# enigma.net
KiCad netlist of a schematic drawn in EAGLE
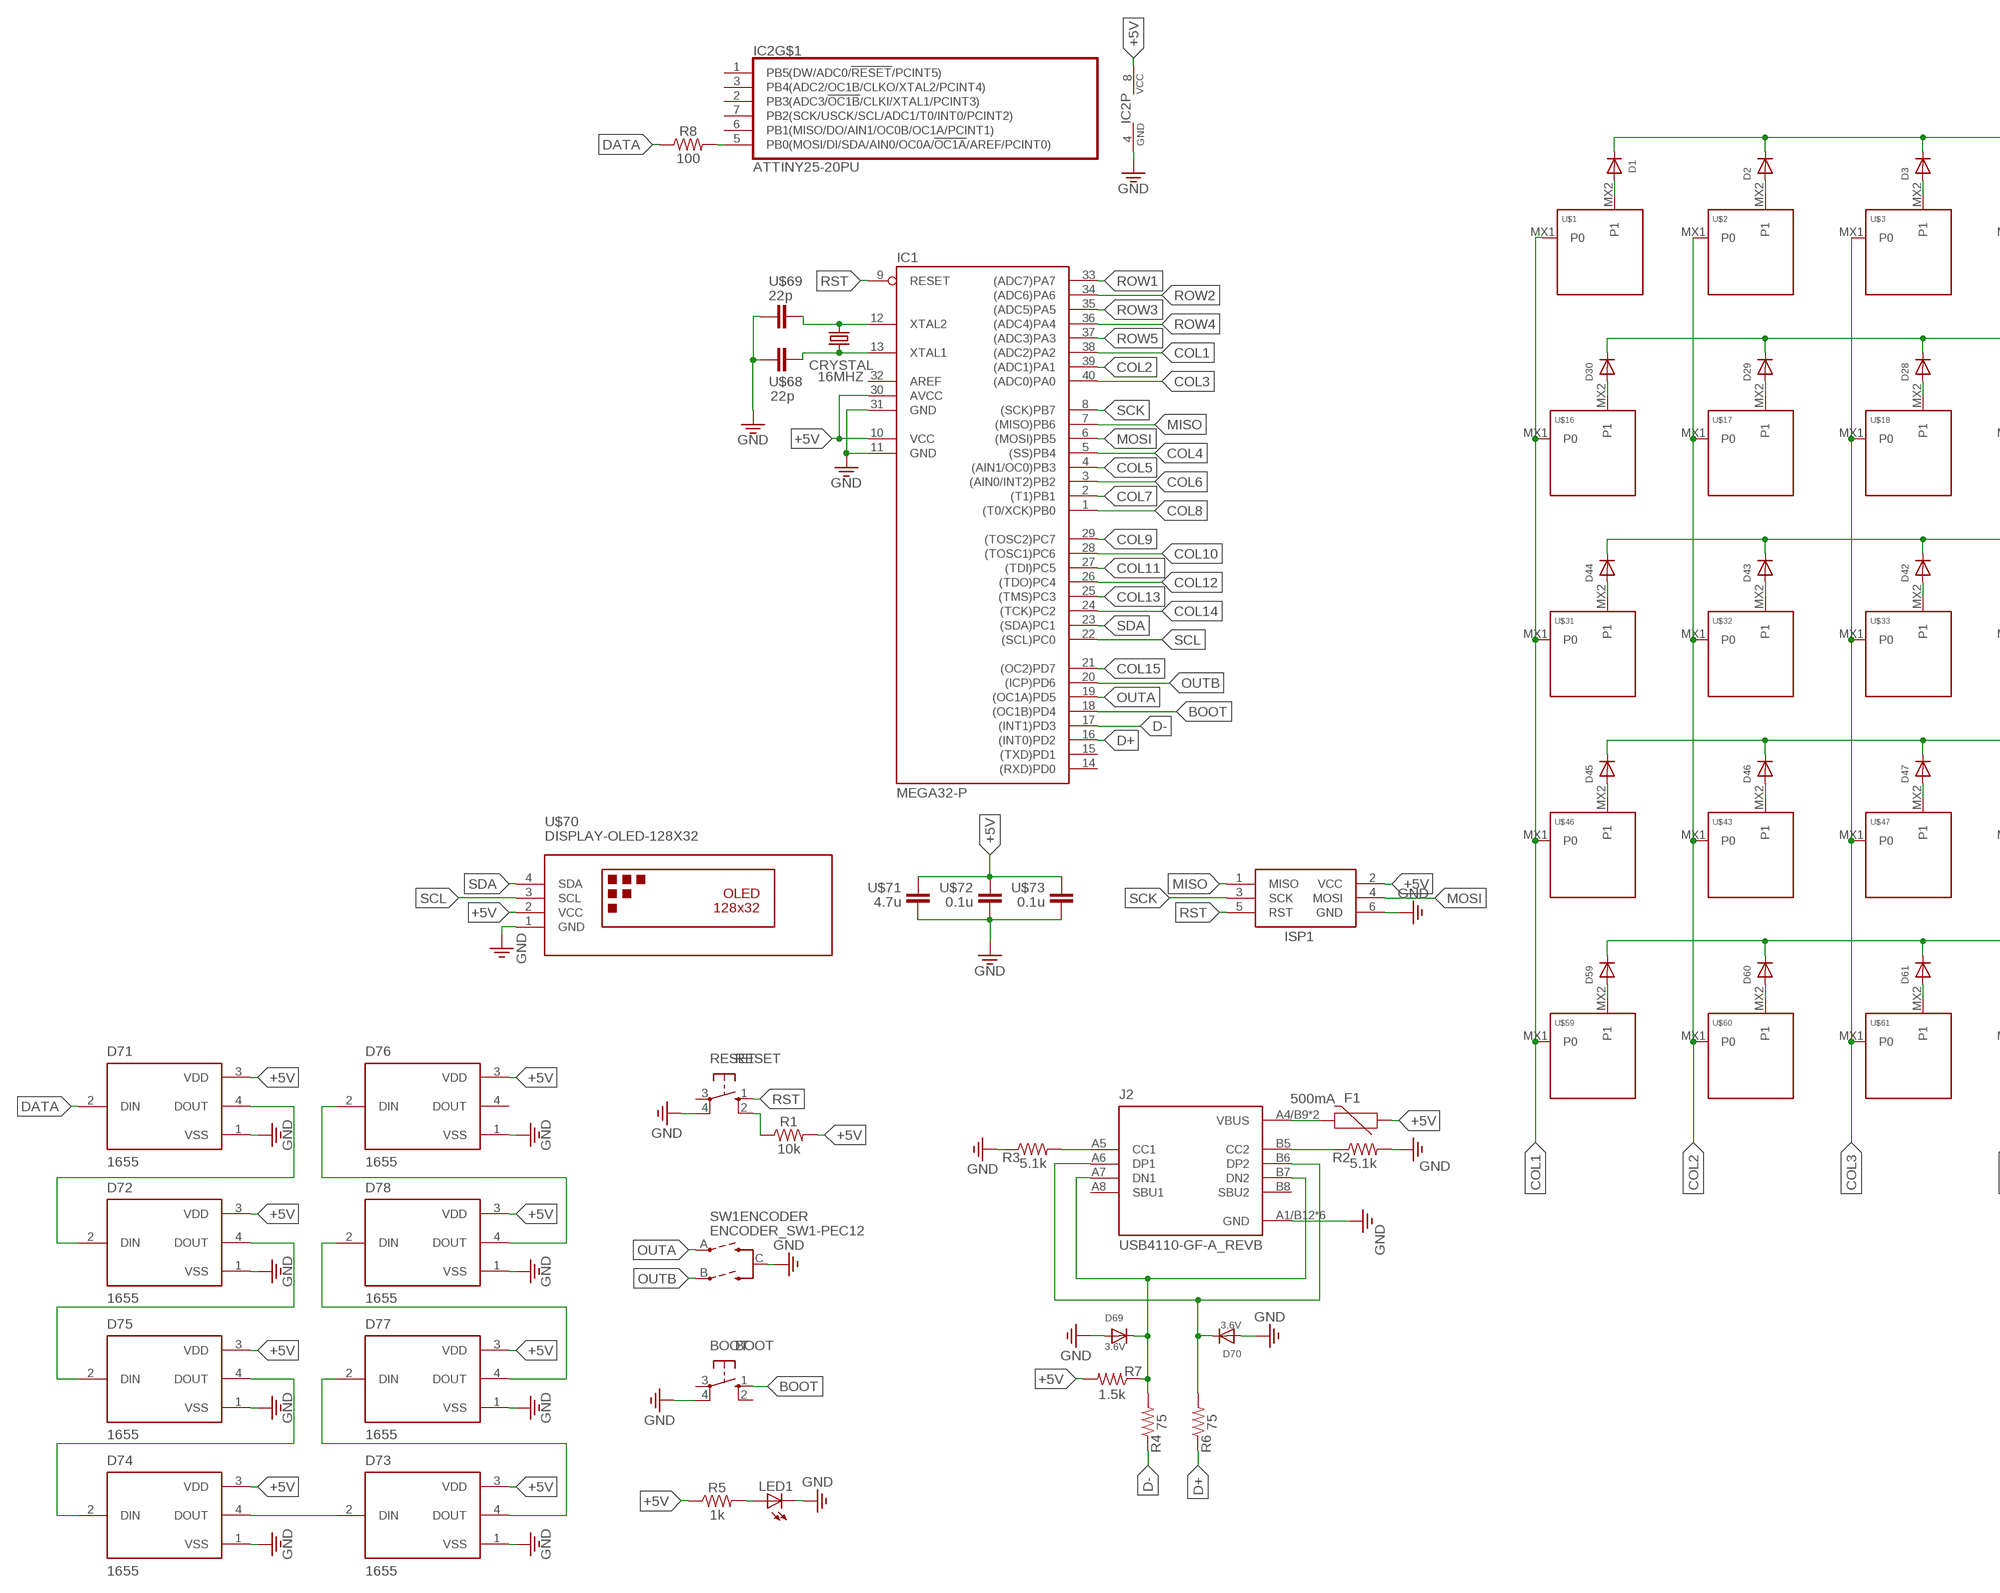
[diagram p0: schematic, sheet 1, part 1 of 2]
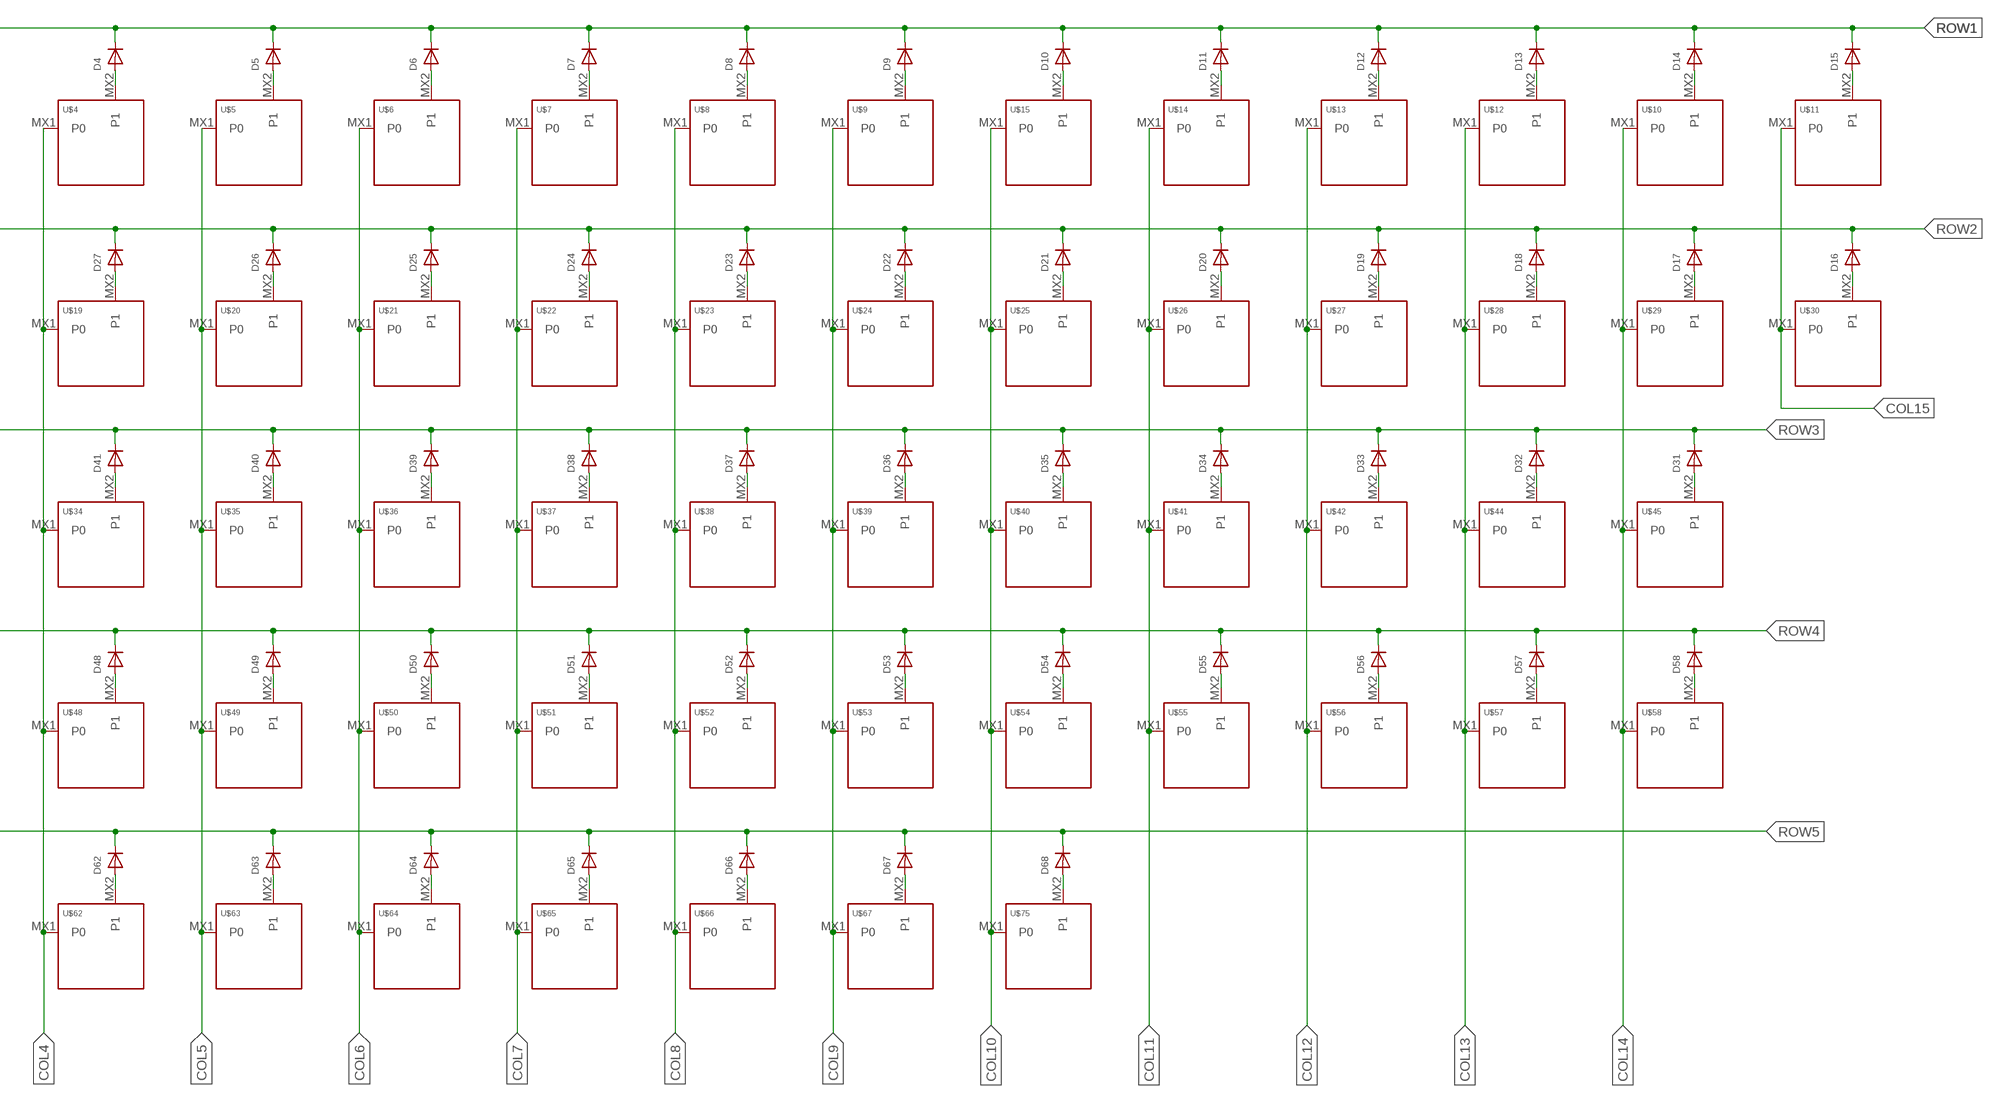
[diagram p1: schematic, sheet 1, part 2 of 2]

(export (version "E")
  (design (tool "Eeschema 10.0.6"))
  (components
    (comp (ref "BOOT")
      (value "BOOT")
      (footprint "eagle-import:B3F-10XX")
      (fields (field (name "MPN") "B3F-1000"))
      (libsource (lib "eagle-import") (part "10-XX"))
    )
    (comp (ref "CRYSTAL")
      (value "16MHZ")
      (footprint "eagle-import:HC49U-V")
      (libsource (lib "eagle-import") (part "CRYSTALHC49U-V"))
    )
    (comp (ref "D1")
      (value "DIODEDO-1N4148")
      (footprint "eagle-import:DO-1N4148")
      (libsource (lib "eagle-import") (part "DIODEDO-1N4148"))
    )
    (comp (ref "D2")
      (value "DIODEDO-1N4148")
      (footprint "eagle-import:DO-1N4148")
      (libsource (lib "eagle-import") (part "DIODEDO-1N4148"))
    )
    (comp (ref "D3")
      (value "DIODEDO-1N4148")
      (footprint "eagle-import:DO-1N4148")
      (libsource (lib "eagle-import") (part "DIODEDO-1N4148"))
    )
    (comp (ref "D4")
      (value "DIODEDO-1N4148")
      (footprint "eagle-import:DO-1N4148")
      (libsource (lib "eagle-import") (part "DIODEDO-1N4148"))
    )
    (comp (ref "D5")
      (value "DIODEDO-1N4148")
      (footprint "eagle-import:DO-1N4148")
      (libsource (lib "eagle-import") (part "DIODEDO-1N4148"))
    )
    (comp (ref "D6")
      (value "DIODEDO-1N4148")
      (footprint "eagle-import:DO-1N4148")
      (libsource (lib "eagle-import") (part "DIODEDO-1N4148"))
    )
    (comp (ref "D7")
      (value "DIODEDO-1N4148")
      (footprint "eagle-import:DO-1N4148")
      (libsource (lib "eagle-import") (part "DIODEDO-1N4148"))
    )
    (comp (ref "D8")
      (value "DIODEDO-1N4148")
      (footprint "eagle-import:DO-1N4148")
      (libsource (lib "eagle-import") (part "DIODEDO-1N4148"))
    )
    (comp (ref "D9")
      (value "DIODEDO-1N4148")
      (footprint "eagle-import:DO-1N4148")
      (libsource (lib "eagle-import") (part "DIODEDO-1N4148"))
    )
    (comp (ref "D10")
      (value "DIODEDO-1N4148")
      (footprint "eagle-import:DO-1N4148")
      (libsource (lib "eagle-import") (part "DIODEDO-1N4148"))
    )
    (comp (ref "D11")
      (value "DIODEDO-1N4148")
      (footprint "eagle-import:DO-1N4148")
      (libsource (lib "eagle-import") (part "DIODEDO-1N4148"))
    )
    (comp (ref "D12")
      (value "DIODEDO-1N4148")
      (footprint "eagle-import:DO-1N4148")
      (libsource (lib "eagle-import") (part "DIODEDO-1N4148"))
    )
    (comp (ref "D13")
      (value "DIODEDO-1N4148")
      (footprint "eagle-import:DO-1N4148")
      (libsource (lib "eagle-import") (part "DIODEDO-1N4148"))
    )
    (comp (ref "D14")
      (value "DIODEDO-1N4148")
      (footprint "eagle-import:DO-1N4148")
      (libsource (lib "eagle-import") (part "DIODEDO-1N4148"))
    )
    (comp (ref "D15")
      (value "DIODEDO-1N4148")
      (footprint "eagle-import:DO-1N4148")
      (libsource (lib "eagle-import") (part "DIODEDO-1N4148"))
    )
    (comp (ref "D16")
      (value "DIODEDO-1N4148")
      (footprint "eagle-import:DO-1N4148")
      (libsource (lib "eagle-import") (part "DIODEDO-1N4148"))
    )
    (comp (ref "D17")
      (value "DIODEDO-1N4148")
      (footprint "eagle-import:DO-1N4148")
      (libsource (lib "eagle-import") (part "DIODEDO-1N4148"))
    )
    (comp (ref "D18")
      (value "DIODEDO-1N4148")
      (footprint "eagle-import:DO-1N4148")
      (libsource (lib "eagle-import") (part "DIODEDO-1N4148"))
    )
    (comp (ref "D19")
      (value "DIODEDO-1N4148")
      (footprint "eagle-import:DO-1N4148")
      (libsource (lib "eagle-import") (part "DIODEDO-1N4148"))
    )
    (comp (ref "D20")
      (value "DIODEDO-1N4148")
      (footprint "eagle-import:DO-1N4148")
      (libsource (lib "eagle-import") (part "DIODEDO-1N4148"))
    )
    (comp (ref "D21")
      (value "DIODEDO-1N4148")
      (footprint "eagle-import:DO-1N4148")
      (libsource (lib "eagle-import") (part "DIODEDO-1N4148"))
    )
    (comp (ref "D22")
      (value "DIODEDO-1N4148")
      (footprint "eagle-import:DO-1N4148")
      (libsource (lib "eagle-import") (part "DIODEDO-1N4148"))
    )
    (comp (ref "D23")
      (value "DIODEDO-1N4148")
      (footprint "eagle-import:DO-1N4148")
      (libsource (lib "eagle-import") (part "DIODEDO-1N4148"))
    )
    (comp (ref "D24")
      (value "DIODEDO-1N4148")
      (footprint "eagle-import:DO-1N4148")
      (libsource (lib "eagle-import") (part "DIODEDO-1N4148"))
    )
    (comp (ref "D25")
      (value "DIODEDO-1N4148")
      (footprint "eagle-import:DO-1N4148")
      (libsource (lib "eagle-import") (part "DIODEDO-1N4148"))
    )
    (comp (ref "D26")
      (value "DIODEDO-1N4148")
      (footprint "eagle-import:DO-1N4148")
      (libsource (lib "eagle-import") (part "DIODEDO-1N4148"))
    )
    (comp (ref "D27")
      (value "DIODEDO-1N4148")
      (footprint "eagle-import:DO-1N4148")
      (libsource (lib "eagle-import") (part "DIODEDO-1N4148"))
    )
    (comp (ref "D28")
      (value "DIODEDO-1N4148")
      (footprint "eagle-import:DO-1N4148")
      (libsource (lib "eagle-import") (part "DIODEDO-1N4148"))
    )
    (comp (ref "D29")
      (value "DIODEDO-1N4148")
      (footprint "eagle-import:DO-1N4148")
      (libsource (lib "eagle-import") (part "DIODEDO-1N4148"))
    )
    (comp (ref "D30")
      (value "DIODEDO-1N4148")
      (footprint "eagle-import:DO-1N4148")
      (libsource (lib "eagle-import") (part "DIODEDO-1N4148"))
    )
    (comp (ref "D31")
      (value "DIODEDO-1N4148")
      (footprint "eagle-import:DO-1N4148")
      (libsource (lib "eagle-import") (part "DIODEDO-1N4148"))
    )
    (comp (ref "D32")
      (value "DIODEDO-1N4148")
      (footprint "eagle-import:DO-1N4148")
      (libsource (lib "eagle-import") (part "DIODEDO-1N4148"))
    )
    (comp (ref "D33")
      (value "DIODEDO-1N4148")
      (footprint "eagle-import:DO-1N4148")
      (libsource (lib "eagle-import") (part "DIODEDO-1N4148"))
    )
    (comp (ref "D34")
      (value "DIODEDO-1N4148")
      (footprint "eagle-import:DO-1N4148")
      (libsource (lib "eagle-import") (part "DIODEDO-1N4148"))
    )
    (comp (ref "D35")
      (value "DIODEDO-1N4148")
      (footprint "eagle-import:DO-1N4148")
      (libsource (lib "eagle-import") (part "DIODEDO-1N4148"))
    )
    (comp (ref "D36")
      (value "DIODEDO-1N4148")
      (footprint "eagle-import:DO-1N4148")
      (libsource (lib "eagle-import") (part "DIODEDO-1N4148"))
    )
    (comp (ref "D37")
      (value "DIODEDO-1N4148")
      (footprint "eagle-import:DO-1N4148")
      (libsource (lib "eagle-import") (part "DIODEDO-1N4148"))
    )
    (comp (ref "D38")
      (value "DIODEDO-1N4148")
      (footprint "eagle-import:DO-1N4148")
      (libsource (lib "eagle-import") (part "DIODEDO-1N4148"))
    )
    (comp (ref "D39")
      (value "DIODEDO-1N4148")
      (footprint "eagle-import:DO-1N4148")
      (libsource (lib "eagle-import") (part "DIODEDO-1N4148"))
    )
    (comp (ref "D40")
      (value "DIODEDO-1N4148")
      (footprint "eagle-import:DO-1N4148")
      (libsource (lib "eagle-import") (part "DIODEDO-1N4148"))
    )
    (comp (ref "D41")
      (value "DIODEDO-1N4148")
      (footprint "eagle-import:DO-1N4148")
      (libsource (lib "eagle-import") (part "DIODEDO-1N4148"))
    )
    (comp (ref "D42")
      (value "DIODEDO-1N4148")
      (footprint "eagle-import:DO-1N4148")
      (libsource (lib "eagle-import") (part "DIODEDO-1N4148"))
    )
    (comp (ref "D43")
      (value "DIODEDO-1N4148")
      (footprint "eagle-import:DO-1N4148")
      (libsource (lib "eagle-import") (part "DIODEDO-1N4148"))
    )
    (comp (ref "D44")
      (value "DIODEDO-1N4148")
      (footprint "eagle-import:DO-1N4148")
      (libsource (lib "eagle-import") (part "DIODEDO-1N4148"))
    )
    (comp (ref "D45")
      (value "DIODEDO-1N4148")
      (footprint "eagle-import:DO-1N4148")
      (libsource (lib "eagle-import") (part "DIODEDO-1N4148"))
    )
    (comp (ref "D46")
      (value "DIODEDO-1N4148")
      (footprint "eagle-import:DO-1N4148")
      (libsource (lib "eagle-import") (part "DIODEDO-1N4148"))
    )
    (comp (ref "D47")
      (value "DIODEDO-1N4148")
      (footprint "eagle-import:DO-1N4148")
      (libsource (lib "eagle-import") (part "DIODEDO-1N4148"))
    )
    (comp (ref "D48")
      (value "DIODEDO-1N4148")
      (footprint "eagle-import:DO-1N4148")
      (libsource (lib "eagle-import") (part "DIODEDO-1N4148"))
    )
    (comp (ref "D49")
      (value "DIODEDO-1N4148")
      (footprint "eagle-import:DO-1N4148")
      (libsource (lib "eagle-import") (part "DIODEDO-1N4148"))
    )
    (comp (ref "D50")
      (value "DIODEDO-1N4148")
      (footprint "eagle-import:DO-1N4148")
      (libsource (lib "eagle-import") (part "DIODEDO-1N4148"))
    )
    (comp (ref "D51")
      (value "DIODEDO-1N4148")
      (footprint "eagle-import:DO-1N4148")
      (libsource (lib "eagle-import") (part "DIODEDO-1N4148"))
    )
    (comp (ref "D52")
      (value "DIODEDO-1N4148")
      (footprint "eagle-import:DO-1N4148")
      (libsource (lib "eagle-import") (part "DIODEDO-1N4148"))
    )
    (comp (ref "D53")
      (value "DIODEDO-1N4148")
      (footprint "eagle-import:DO-1N4148")
      (libsource (lib "eagle-import") (part "DIODEDO-1N4148"))
    )
    (comp (ref "D54")
      (value "DIODEDO-1N4148")
      (footprint "eagle-import:DO-1N4148")
      (libsource (lib "eagle-import") (part "DIODEDO-1N4148"))
    )
    (comp (ref "D55")
      (value "DIODEDO-1N4148")
      (footprint "eagle-import:DO-1N4148")
      (libsource (lib "eagle-import") (part "DIODEDO-1N4148"))
    )
    (comp (ref "D56")
      (value "DIODEDO-1N4148")
      (footprint "eagle-import:DO-1N4148")
      (libsource (lib "eagle-import") (part "DIODEDO-1N4148"))
    )
    (comp (ref "D57")
      (value "DIODEDO-1N4148")
      (footprint "eagle-import:DO-1N4148")
      (libsource (lib "eagle-import") (part "DIODEDO-1N4148"))
    )
    (comp (ref "D58")
      (value "DIODEDO-1N4148")
      (footprint "eagle-import:DO-1N4148")
      (libsource (lib "eagle-import") (part "DIODEDO-1N4148"))
    )
    (comp (ref "D59")
      (value "DIODEDO-1N4148")
      (footprint "eagle-import:DO-1N4148")
      (libsource (lib "eagle-import") (part "DIODEDO-1N4148"))
    )
    (comp (ref "D60")
      (value "DIODEDO-1N4148")
      (footprint "eagle-import:DO-1N4148")
      (libsource (lib "eagle-import") (part "DIODEDO-1N4148"))
    )
    (comp (ref "D61")
      (value "DIODEDO-1N4148")
      (footprint "eagle-import:DO-1N4148")
      (libsource (lib "eagle-import") (part "DIODEDO-1N4148"))
    )
    (comp (ref "D62")
      (value "DIODEDO-1N4148")
      (footprint "eagle-import:DO-1N4148")
      (libsource (lib "eagle-import") (part "DIODEDO-1N4148"))
    )
    (comp (ref "D63")
      (value "DIODEDO-1N4148")
      (footprint "eagle-import:DO-1N4148")
      (libsource (lib "eagle-import") (part "DIODEDO-1N4148"))
    )
    (comp (ref "D64")
      (value "DIODEDO-1N4148")
      (footprint "eagle-import:DO-1N4148")
      (libsource (lib "eagle-import") (part "DIODEDO-1N4148"))
    )
    (comp (ref "D65")
      (value "DIODEDO-1N4148")
      (footprint "eagle-import:DO-1N4148")
      (libsource (lib "eagle-import") (part "DIODEDO-1N4148"))
    )
    (comp (ref "D66")
      (value "DIODEDO-1N4148")
      (footprint "eagle-import:DO-1N4148")
      (libsource (lib "eagle-import") (part "DIODEDO-1N4148"))
    )
    (comp (ref "D67")
      (value "DIODEDO-1N4148")
      (footprint "eagle-import:DO-1N4148")
      (libsource (lib "eagle-import") (part "DIODEDO-1N4148"))
    )
    (comp (ref "D68")
      (value "DIODEDO-1N4148")
      (footprint "eagle-import:DO-1N4148")
      (libsource (lib "eagle-import") (part "DIODEDO-1N4148"))
    )
    (comp (ref "D69")
      (value "3.6V")
      (footprint "eagle-import:DO-1N4148")
      (libsource (lib "eagle-import") (part "DIODEDO-1N4148"))
    )
    (comp (ref "D70")
      (value "3.6V")
      (footprint "eagle-import:DO-1N4148")
      (libsource (lib "eagle-import") (part "DIODEDO-1N4148"))
    )
    (comp (ref "D71")
      (value "1655")
      (footprint "eagle-import:LED_1655")
      (fields (field (name "MF") "Adafruit"))
      (libsource (lib "eagle-import") (part "1655"))
    )
    (comp (ref "D72")
      (value "1655")
      (footprint "eagle-import:LED_1655")
      (fields (field (name "MF") "Adafruit"))
      (libsource (lib "eagle-import") (part "1655"))
    )
    (comp (ref "D73")
      (value "1655")
      (footprint "eagle-import:LED_1655")
      (fields (field (name "MF") "Adafruit"))
      (libsource (lib "eagle-import") (part "1655"))
    )
    (comp (ref "D74")
      (value "1655")
      (footprint "eagle-import:LED_1655")
      (fields (field (name "MF") "Adafruit"))
      (libsource (lib "eagle-import") (part "1655"))
    )
    (comp (ref "D75")
      (value "1655")
      (footprint "eagle-import:LED_1655")
      (fields (field (name "MF") "Adafruit"))
      (libsource (lib "eagle-import") (part "1655"))
    )
    (comp (ref "D76")
      (value "1655")
      (footprint "eagle-import:LED_1655")
      (fields (field (name "MF") "Adafruit"))
      (libsource (lib "eagle-import") (part "1655"))
    )
    (comp (ref "D77")
      (value "1655")
      (footprint "eagle-import:LED_1655")
      (fields (field (name "MF") "Adafruit"))
      (libsource (lib "eagle-import") (part "1655"))
    )
    (comp (ref "D78")
      (value "1655")
      (footprint "eagle-import:LED_1655")
      (fields (field (name "MF") "Adafruit"))
      (libsource (lib "eagle-import") (part "1655"))
    )
    (comp (ref "F1")
      (value "500mA")
      (footprint "eagle-import:PTH")
      (libsource (lib "eagle-import") (part "PPTC_PTH"))
    )
    (comp (ref "IC1")
      (value "MEGA32-P")
      (footprint "eagle-import:DIL40")
      (fields (field (name "MPN") "ATMEGA32-16PU"))
      (libsource (lib "eagle-import") (part "MEGA32-P"))
    )
    (comp (ref "IC2")
      (value "ATTINY25-20PU")
      (footprint "eagle-import:DIL08")
      (libsource (lib "eagle-import") (part "ATTINY5-20PU2"))
    )
    (comp (ref "ISP1")
      (value "AVRISP-6")
      (footprint "eagle-import:AVRISP")
      (libsource (lib "eagle-import") (part "AVRISP-6"))
    )
    (comp (ref "J2")
      (value "USB4110-GF-A_REVB")
      (footprint "eagle-import:GCT_USB4110-GF-A_REVB")
      (fields (field (name "MF") "GCT") (field (name "MP") "USB4110-GF-A"))
      (libsource (lib "eagle-import") (part "USB4110-GF-A_REVB"))
    )
    (comp (ref "LED1")
      (value "LED5MM")
      (footprint "eagle-import:LED5MM")
      (libsource (lib "eagle-import") (part "LED5MM"))
    )
    (comp (ref "R1")
      (value "10k")
      (footprint "eagle-import:AXIAL-0.3")
      (libsource (lib "eagle-import") (part "RESISTORAXIAL-0.3"))
    )
    (comp (ref "R2")
      (value "5.1k")
      (footprint "eagle-import:AXIAL-0.3")
      (libsource (lib "eagle-import") (part "RESISTORAXIAL-0.3"))
    )
    (comp (ref "R3")
      (value "5.1k")
      (footprint "eagle-import:AXIAL-0.3")
      (libsource (lib "eagle-import") (part "RESISTORAXIAL-0.3"))
    )
    (comp (ref "R4")
      (value "75")
      (footprint "eagle-import:AXIAL-0.3")
      (libsource (lib "eagle-import") (part "RESISTORAXIAL-0.3"))
    )
    (comp (ref "R5")
      (value "1k")
      (footprint "eagle-import:AXIAL-0.3")
      (libsource (lib "eagle-import") (part "RESISTORAXIAL-0.3"))
    )
    (comp (ref "R6")
      (value "75")
      (footprint "eagle-import:AXIAL-0.3")
      (libsource (lib "eagle-import") (part "RESISTORAXIAL-0.3"))
    )
    (comp (ref "R7")
      (value "1.5k")
      (footprint "eagle-import:AXIAL-0.3")
      (libsource (lib "eagle-import") (part "RESISTORAXIAL-0.3"))
    )
    (comp (ref "R8")
      (value "100")
      (footprint "eagle-import:AXIAL-0.3")
      (libsource (lib "eagle-import") (part "RESISTORAXIAL-0.3"))
    )
    (comp (ref "RESET")
      (value "RESET")
      (footprint "eagle-import:B3F-10XX")
      (fields (field (name "MPN") "B3F-1000"))
      (libsource (lib "eagle-import") (part "10-XX"))
    )
    (comp (ref "SW1")
      (value "ENCODER_SW1-PEC12")
      (footprint "eagle-import:PEC12_INCREMENTAL_ENCODER")
      (libsource (lib "eagle-import") (part "ENCODER_SW1-PEC12"))
    )
    (comp (ref "U$1")
      (value "KEYSWITCH-PLAIN-MXHSPCB-1U")
      (footprint "eagle-import:MXHSPCB-1U")
      (libsource (lib "eagle-import") (part "KEYSWITCH-PLAIN-MXHSPCB-1U"))
    )
    (comp (ref "U$2")
      (value "KEYSWITCH-PLAIN-MXHSPCB-1U")
      (footprint "eagle-import:MXHSPCB-1U")
      (libsource (lib "eagle-import") (part "KEYSWITCH-PLAIN-MXHSPCB-1U"))
    )
    (comp (ref "U$3")
      (value "KEYSWITCH-PLAIN-MXHSPCB-1U")
      (footprint "eagle-import:MXHSPCB-1U")
      (libsource (lib "eagle-import") (part "KEYSWITCH-PLAIN-MXHSPCB-1U"))
    )
    (comp (ref "U$4")
      (value "KEYSWITCH-PLAIN-MXHSPCB-1U")
      (footprint "eagle-import:MXHSPCB-1U")
      (libsource (lib "eagle-import") (part "KEYSWITCH-PLAIN-MXHSPCB-1U"))
    )
    (comp (ref "U$5")
      (value "KEYSWITCH-PLAIN-MXHSPCB-1U")
      (footprint "eagle-import:MXHSPCB-1U")
      (libsource (lib "eagle-import") (part "KEYSWITCH-PLAIN-MXHSPCB-1U"))
    )
    (comp (ref "U$6")
      (value "KEYSWITCH-PLAIN-MXHSPCB-1U")
      (footprint "eagle-import:MXHSPCB-1U")
      (libsource (lib "eagle-import") (part "KEYSWITCH-PLAIN-MXHSPCB-1U"))
    )
    (comp (ref "U$7")
      (value "KEYSWITCH-PLAIN-MXHSPCB-1U")
      (footprint "eagle-import:MXHSPCB-1U")
      (libsource (lib "eagle-import") (part "KEYSWITCH-PLAIN-MXHSPCB-1U"))
    )
    (comp (ref "U$8")
      (value "KEYSWITCH-PLAIN-MXHSPCB-1U")
      (footprint "eagle-import:MXHSPCB-1U")
      (libsource (lib "eagle-import") (part "KEYSWITCH-PLAIN-MXHSPCB-1U"))
    )
    (comp (ref "U$9")
      (value "KEYSWITCH-PLAIN-MXHSPCB-1U")
      (footprint "eagle-import:MXHSPCB-1U")
      (libsource (lib "eagle-import") (part "KEYSWITCH-PLAIN-MXHSPCB-1U"))
    )
    (comp (ref "U$10")
      (value "KEYSWITCH-PLAIN-MXHSPCB-2U")
      (footprint "eagle-import:MXHSPCB-2U")
      (libsource (lib "eagle-import") (part "KEYSWITCH-PLAIN-MXHSPCB-2U"))
    )
    (comp (ref "U$11")
      (value "KEYSWITCH-PLAIN-MXHSPCB-1U")
      (footprint "eagle-import:MXHSPCB-1U")
      (libsource (lib "eagle-import") (part "KEYSWITCH-PLAIN-MXHSPCB-1U"))
    )
    (comp (ref "U$12")
      (value "KEYSWITCH-PLAIN-MXHSPCB-1U")
      (footprint "eagle-import:MXHSPCB-1U")
      (libsource (lib "eagle-import") (part "KEYSWITCH-PLAIN-MXHSPCB-1U"))
    )
    (comp (ref "U$13")
      (value "KEYSWITCH-PLAIN-MXHSPCB-1U")
      (footprint "eagle-import:MXHSPCB-1U")
      (libsource (lib "eagle-import") (part "KEYSWITCH-PLAIN-MXHSPCB-1U"))
    )
    (comp (ref "U$14")
      (value "KEYSWITCH-PLAIN-MXHSPCB-1U")
      (footprint "eagle-import:MXHSPCB-1U")
      (libsource (lib "eagle-import") (part "KEYSWITCH-PLAIN-MXHSPCB-1U"))
    )
    (comp (ref "U$15")
      (value "KEYSWITCH-PLAIN-MXHSPCB-1U")
      (footprint "eagle-import:MXHSPCB-1U")
      (libsource (lib "eagle-import") (part "KEYSWITCH-PLAIN-MXHSPCB-1U"))
    )
    (comp (ref "U$16")
      (value "KEYSWITCH-PLAIN-MXHSPCB-1U")
      (footprint "eagle-import:MXHSPCB-1U")
      (libsource (lib "eagle-import") (part "KEYSWITCH-PLAIN-MXHSPCB-1U"))
    )
    (comp (ref "U$17")
      (value "KEYSWITCH-PLAIN-MXHSPCB-1U")
      (footprint "eagle-import:MXHSPCB-1U")
      (libsource (lib "eagle-import") (part "KEYSWITCH-PLAIN-MXHSPCB-1U"))
    )
    (comp (ref "U$18")
      (value "KEYSWITCH-PLAIN-MXHSPCB-1U")
      (footprint "eagle-import:MXHSPCB-1U")
      (libsource (lib "eagle-import") (part "KEYSWITCH-PLAIN-MXHSPCB-1U"))
    )
    (comp (ref "U$19")
      (value "KEYSWITCH-PLAIN-MXHSPCB-1U")
      (footprint "eagle-import:MXHSPCB-1U")
      (libsource (lib "eagle-import") (part "KEYSWITCH-PLAIN-MXHSPCB-1U"))
    )
    (comp (ref "U$20")
      (value "KEYSWITCH-PLAIN-MXHSPCB-1U")
      (footprint "eagle-import:MXHSPCB-1U")
      (libsource (lib "eagle-import") (part "KEYSWITCH-PLAIN-MXHSPCB-1U"))
    )
    (comp (ref "U$21")
      (value "KEYSWITCH-PLAIN-MXHSPCB-1U")
      (footprint "eagle-import:MXHSPCB-1U")
      (libsource (lib "eagle-import") (part "KEYSWITCH-PLAIN-MXHSPCB-1U"))
    )
    (comp (ref "U$22")
      (value "KEYSWITCH-PLAIN-MXHSPCB-1U")
      (footprint "eagle-import:MXHSPCB-1U")
      (libsource (lib "eagle-import") (part "KEYSWITCH-PLAIN-MXHSPCB-1U"))
    )
    (comp (ref "U$23")
      (value "KEYSWITCH-PLAIN-MXHSPCB-1U")
      (footprint "eagle-import:MXHSPCB-1U")
      (libsource (lib "eagle-import") (part "KEYSWITCH-PLAIN-MXHSPCB-1U"))
    )
    (comp (ref "U$24")
      (value "KEYSWITCH-PLAIN-MXHSPCB-1U")
      (footprint "eagle-import:MXHSPCB-1U")
      (libsource (lib "eagle-import") (part "KEYSWITCH-PLAIN-MXHSPCB-1U"))
    )
    (comp (ref "U$25")
      (value "KEYSWITCH-PLAIN-MXHSPCB-1U")
      (footprint "eagle-import:MXHSPCB-1U")
      (libsource (lib "eagle-import") (part "KEYSWITCH-PLAIN-MXHSPCB-1U"))
    )
    (comp (ref "U$26")
      (value "KEYSWITCH-PLAIN-MXHSPCB-1U")
      (footprint "eagle-import:MXHSPCB-1U")
      (libsource (lib "eagle-import") (part "KEYSWITCH-PLAIN-MXHSPCB-1U"))
    )
    (comp (ref "U$27")
      (value "KEYSWITCH-PLAIN-MXHSPCB-1U")
      (footprint "eagle-import:MXHSPCB-1U")
      (libsource (lib "eagle-import") (part "KEYSWITCH-PLAIN-MXHSPCB-1U"))
    )
    (comp (ref "U$28")
      (value "KEYSWITCH-PLAIN-MXHSPCB-1U")
      (footprint "eagle-import:MXHSPCB-1U")
      (libsource (lib "eagle-import") (part "KEYSWITCH-PLAIN-MXHSPCB-1U"))
    )
    (comp (ref "U$29")
      (value "KEYSWITCH-PLAIN-MXHSPCB-1U")
      (footprint "eagle-import:MXHSPCB-1U")
      (libsource (lib "eagle-import") (part "KEYSWITCH-PLAIN-MXHSPCB-1U"))
    )
    (comp (ref "U$30")
      (value "KEYSWITCH-PLAIN-MXHSPCB-1U")
      (footprint "eagle-import:MXHSPCB-1U")
      (libsource (lib "eagle-import") (part "KEYSWITCH-PLAIN-MXHSPCB-1U"))
    )
    (comp (ref "U$31")
      (value "KEYSWITCH-PLAIN-MXHSPCB-1U")
      (footprint "eagle-import:MXHSPCB-1U")
      (libsource (lib "eagle-import") (part "KEYSWITCH-PLAIN-MXHSPCB-1U"))
    )
    (comp (ref "U$32")
      (value "KEYSWITCH-PLAIN-MXHSPCB-1U")
      (footprint "eagle-import:MXHSPCB-1U")
      (libsource (lib "eagle-import") (part "KEYSWITCH-PLAIN-MXHSPCB-1U"))
    )
    (comp (ref "U$33")
      (value "KEYSWITCH-PLAIN-MXHSPCB-1U")
      (footprint "eagle-import:MXHSPCB-1U")
      (libsource (lib "eagle-import") (part "KEYSWITCH-PLAIN-MXHSPCB-1U"))
    )
    (comp (ref "U$34")
      (value "KEYSWITCH-PLAIN-MXHSPCB-1U")
      (footprint "eagle-import:MXHSPCB-1U")
      (libsource (lib "eagle-import") (part "KEYSWITCH-PLAIN-MXHSPCB-1U"))
    )
    (comp (ref "U$35")
      (value "KEYSWITCH-PLAIN-MXHSPCB-1U")
      (footprint "eagle-import:MXHSPCB-1U")
      (libsource (lib "eagle-import") (part "KEYSWITCH-PLAIN-MXHSPCB-1U"))
    )
    (comp (ref "U$36")
      (value "KEYSWITCH-PLAIN-MXHSPCB-1U")
      (footprint "eagle-import:MXHSPCB-1U")
      (libsource (lib "eagle-import") (part "KEYSWITCH-PLAIN-MXHSPCB-1U"))
    )
    (comp (ref "U$37")
      (value "KEYSWITCH-PLAIN-MXHSPCB-1U")
      (footprint "eagle-import:MXHSPCB-1U")
      (libsource (lib "eagle-import") (part "KEYSWITCH-PLAIN-MXHSPCB-1U"))
    )
    (comp (ref "U$38")
      (value "KEYSWITCH-PLAIN-MXHSPCB-1U")
      (footprint "eagle-import:MXHSPCB-1U")
      (libsource (lib "eagle-import") (part "KEYSWITCH-PLAIN-MXHSPCB-1U"))
    )
    (comp (ref "U$39")
      (value "KEYSWITCH-PLAIN-MXHSPCB-1U")
      (footprint "eagle-import:MXHSPCB-1U")
      (libsource (lib "eagle-import") (part "KEYSWITCH-PLAIN-MXHSPCB-1U"))
    )
    (comp (ref "U$40")
      (value "KEYSWITCH-PLAIN-MXHSPCB-1U")
      (footprint "eagle-import:MXHSPCB-1U")
      (libsource (lib "eagle-import") (part "KEYSWITCH-PLAIN-MXHSPCB-1U"))
    )
    (comp (ref "U$41")
      (value "KEYSWITCH-PLAIN-MXHSPCB-1U")
      (footprint "eagle-import:MXHSPCB-1U")
      (libsource (lib "eagle-import") (part "KEYSWITCH-PLAIN-MXHSPCB-1U"))
    )
    (comp (ref "U$42")
      (value "KEYSWITCH-PLAIN-MXHSPCB-1U")
      (footprint "eagle-import:MXHSPCB-1U")
      (libsource (lib "eagle-import") (part "KEYSWITCH-PLAIN-MXHSPCB-1U"))
    )
    (comp (ref "U$43")
      (value "KEYSWITCH-PLAIN-MXHSPCB-1U")
      (footprint "eagle-import:MXHSPCB-1U")
      (libsource (lib "eagle-import") (part "KEYSWITCH-PLAIN-MXHSPCB-1U"))
    )
    (comp (ref "U$44")
      (value "KEYSWITCH-PLAIN-MXHSPCB-2U-FLIPPED")
      (footprint "eagle-import:MXHSPCB-2U-FLIPPED")
      (libsource (lib "eagle-import") (part "KEYSWITCH-PLAIN-MXHSPCB-2U-FLIPPED"))
    )
    (comp (ref "U$45")
      (value "KEYSWITCH-PLAIN-MXHSPCB-1U")
      (footprint "eagle-import:MXHSPCB-1U")
      (libsource (lib "eagle-import") (part "KEYSWITCH-PLAIN-MXHSPCB-1U"))
    )
    (comp (ref "U$46")
      (value "KEYSWITCH-PLAIN-MXHSPCB-2U-FLIPPED")
      (footprint "eagle-import:MXHSPCB-2U-FLIPPED")
      (libsource (lib "eagle-import") (part "KEYSWITCH-PLAIN-MXHSPCB-2U-FLIPPED"))
    )
    (comp (ref "U$47")
      (value "KEYSWITCH-PLAIN-MXHSPCB-1U")
      (footprint "eagle-import:MXHSPCB-1U")
      (libsource (lib "eagle-import") (part "KEYSWITCH-PLAIN-MXHSPCB-1U"))
    )
    (comp (ref "U$48")
      (value "KEYSWITCH-PLAIN-MXHSPCB-1U")
      (footprint "eagle-import:MXHSPCB-1U")
      (libsource (lib "eagle-import") (part "KEYSWITCH-PLAIN-MXHSPCB-1U"))
    )
    (comp (ref "U$49")
      (value "KEYSWITCH-PLAIN-MXHSPCB-1U")
      (footprint "eagle-import:MXHSPCB-1U")
      (libsource (lib "eagle-import") (part "KEYSWITCH-PLAIN-MXHSPCB-1U"))
    )
    (comp (ref "U$50")
      (value "KEYSWITCH-PLAIN-MXHSPCB-1U")
      (footprint "eagle-import:MXHSPCB-1U")
      (libsource (lib "eagle-import") (part "KEYSWITCH-PLAIN-MXHSPCB-1U"))
    )
    (comp (ref "U$51")
      (value "KEYSWITCH-PLAIN-MXHSPCB-1U")
      (footprint "eagle-import:MXHSPCB-1U")
      (libsource (lib "eagle-import") (part "KEYSWITCH-PLAIN-MXHSPCB-1U"))
    )
    (comp (ref "U$52")
      (value "KEYSWITCH-PLAIN-MXHSPCB-1U")
      (footprint "eagle-import:MXHSPCB-1U")
      (libsource (lib "eagle-import") (part "KEYSWITCH-PLAIN-MXHSPCB-1U"))
    )
    (comp (ref "U$53")
      (value "KEYSWITCH-PLAIN-MXHSPCB-1U")
      (footprint "eagle-import:MXHSPCB-1U")
      (libsource (lib "eagle-import") (part "KEYSWITCH-PLAIN-MXHSPCB-1U"))
    )
    (comp (ref "U$54")
      (value "KEYSWITCH-PLAIN-MXHSPCB-1U")
      (footprint "eagle-import:MXHSPCB-1U")
      (libsource (lib "eagle-import") (part "KEYSWITCH-PLAIN-MXHSPCB-1U"))
    )
    (comp (ref "U$55")
      (value "KEYSWITCH-PLAIN-MXHSPCB-1U")
      (footprint "eagle-import:MXHSPCB-1U")
      (libsource (lib "eagle-import") (part "KEYSWITCH-PLAIN-MXHSPCB-1U"))
    )
    (comp (ref "U$56")
      (value "KEYSWITCH-PLAIN-MXHSPCB-1U")
      (footprint "eagle-import:MXHSPCB-1U")
      (libsource (lib "eagle-import") (part "KEYSWITCH-PLAIN-MXHSPCB-1U"))
    )
    (comp (ref "U$57")
      (value "KEYSWITCH-PLAIN-MXHSPCB-1U")
      (footprint "eagle-import:MXHSPCB-1U")
      (libsource (lib "eagle-import") (part "KEYSWITCH-PLAIN-MXHSPCB-1U"))
    )
    (comp (ref "U$58")
      (value "KEYSWITCH-PLAIN-MXHSPCB-1U")
      (footprint "eagle-import:MXHSPCB-1U")
      (libsource (lib "eagle-import") (part "KEYSWITCH-PLAIN-MXHSPCB-1U"))
    )
    (comp (ref "U$59")
      (value "KEYSWITCH-PLAIN-MXHSPCB-1U")
      (footprint "eagle-import:MXHSPCB-1U")
      (libsource (lib "eagle-import") (part "KEYSWITCH-PLAIN-MXHSPCB-1U"))
    )
    (comp (ref "U$60")
      (value "KEYSWITCH-PLAIN-MXHSPCB-1U")
      (footprint "eagle-import:MXHSPCB-1U")
      (libsource (lib "eagle-import") (part "KEYSWITCH-PLAIN-MXHSPCB-1U"))
    )
    (comp (ref "U$61")
      (value "KEYSWITCH-PLAIN-MXHSPCB-1U")
      (footprint "eagle-import:MXHSPCB-1U")
      (libsource (lib "eagle-import") (part "KEYSWITCH-PLAIN-MXHSPCB-1U"))
    )
    (comp (ref "U$62")
      (value "KEYSWITCH-PLAIN-MXHSPCB-6.25U-FLIPPED")
      (footprint "eagle-import:MXHSPCB-6.25U-FLIPPED")
      (libsource (lib "eagle-import") (part "KEYSWITCH-PLAIN-MXHSPCB-6.25U-FLIPPED"))
    )
    (comp (ref "U$63")
      (value "KEYSWITCH-PLAIN-MXHSPCB-1U")
      (footprint "eagle-import:MXHSPCB-1U")
      (libsource (lib "eagle-import") (part "KEYSWITCH-PLAIN-MXHSPCB-1U"))
    )
    (comp (ref "U$64")
      (value "KEYSWITCH-PLAIN-MXHSPCB-1U")
      (footprint "eagle-import:MXHSPCB-1U")
      (libsource (lib "eagle-import") (part "KEYSWITCH-PLAIN-MXHSPCB-1U"))
    )
    (comp (ref "U$65")
      (value "KEYSWITCH-PLAIN-MXHSPCB-1U")
      (footprint "eagle-import:MXHSPCB-1U")
      (libsource (lib "eagle-import") (part "KEYSWITCH-PLAIN-MXHSPCB-1U"))
    )
    (comp (ref "U$66")
      (value "KEYSWITCH-PLAIN-MXHSPCB-1U")
      (footprint "eagle-import:MXHSPCB-1U")
      (libsource (lib "eagle-import") (part "KEYSWITCH-PLAIN-MXHSPCB-1U"))
    )
    (comp (ref "U$67")
      (value "KEYSWITCH-PLAIN-MXHSPCB-1U")
      (footprint "eagle-import:MXHSPCB-1U")
      (libsource (lib "eagle-import") (part "KEYSWITCH-PLAIN-MXHSPCB-1U"))
    )
    (comp (ref "U$68")
      (value "22p")
      (footprint "eagle-import:CAP-TH")
      (libsource (lib "eagle-import") (part "CAP"))
    )
    (comp (ref "U$69")
      (value "22p")
      (footprint "eagle-import:CAP-TH")
      (libsource (lib "eagle-import") (part "CAP"))
    )
    (comp (ref "U$70")
      (value "DISPLAY-OLED-128X32")
      (footprint "eagle-import:DISPLAY-OLED-128X32")
      (libsource (lib "eagle-import") (part "DISPLAY-OLED-128X32"))
    )
    (comp (ref "U$71")
      (value "4.7u")
      (footprint "eagle-import:CAP-TH")
      (libsource (lib "eagle-import") (part "CAP"))
    )
    (comp (ref "U$72")
      (value "0.1u")
      (footprint "eagle-import:CAP-TH")
      (libsource (lib "eagle-import") (part "CAP"))
    )
    (comp (ref "U$73")
      (value "0.1u")
      (footprint "eagle-import:CAP-TH")
      (libsource (lib "eagle-import") (part "CAP"))
    )
    (comp (ref "U$75")
      (value "KEYSWITCH-PLAIN-MXHSPCB-1U")
      (footprint "eagle-import:MXHSPCB-1U")
      (libsource (lib "eagle-import") (part "KEYSWITCH-PLAIN-MXHSPCB-1U"))
    )
  )
  (nets
    (net (code "1") (name "+5V") (class "Default")
      (node (ref "D71") (pin "3") (pinfunction "VDD_3") (pintype "power_in"))
      (node (ref "D72") (pin "3") (pinfunction "VDD_3") (pintype "power_in"))
      (node (ref "D73") (pin "3") (pinfunction "VDD_3") (pintype "power_in"))
      (node (ref "D74") (pin "3") (pinfunction "VDD_3") (pintype "power_in"))
      (node (ref "D75") (pin "3") (pinfunction "VDD_3") (pintype "power_in"))
      (node (ref "D76") (pin "3") (pinfunction "VDD_3") (pintype "power_in"))
      (node (ref "D77") (pin "3") (pinfunction "VDD_3") (pintype "power_in"))
      (node (ref "D78") (pin "3") (pinfunction "VDD_3") (pintype "power_in"))
      (node (ref "F1") (pin "P$1") (pinfunction "1_P$1") (pintype "bidirectional"))
      (node (ref "IC1") (pin "10") (pinfunction "VCC_10") (pintype "power_in"))
      (node (ref "IC1") (pin "30") (pinfunction "AVCC_30") (pintype "power_in"))
      (node (ref "IC2") (pin "8") (pinfunction "VCC_8") (pintype "power_in"))
      (node (ref "ISP1") (pin "2") (pinfunction "VCC_2") (pintype "power_in"))
      (node (ref "R1") (pin "P$2") (pinfunction "2_P$2") (pintype "passive"))
      (node (ref "R5") (pin "P$1") (pinfunction "1_P$1") (pintype "passive"))
      (node (ref "R7") (pin "P$2") (pinfunction "2_P$2") (pintype "passive"))
      (node (ref "U$70") (pin "2") (pinfunction "VCC_2") (pintype "power_in"))
      (node (ref "U$71") (pin "2") (pinfunction "2_2") (pintype "passive"))
      (node (ref "U$72") (pin "2") (pinfunction "2_2") (pintype "passive"))
      (node (ref "U$73") (pin "2") (pinfunction "2_2") (pintype "passive"))
    )
    (net (code "2") (name "BOOT") (class "Default")
      (node (ref "BOOT") (pin "1") (pinfunction "S_1") (pintype "passive"))
      (node (ref "IC1") (pin "18") (pinfunction "(OC1B)PD4_18") (pintype "bidirectional"))
    )
    (net (code "3") (name "COL1") (class "Default")
      (node (ref "IC1") (pin "38") (pinfunction "(ADC2)PA2_38") (pintype "bidirectional"))
      (node (ref "U$1") (pin "MX1") (pinfunction "P0_MX1") (pintype "bidirectional"))
      (node (ref "U$16") (pin "MX1") (pinfunction "P0_MX1") (pintype "bidirectional"))
      (node (ref "U$31") (pin "MX1") (pinfunction "P0_MX1") (pintype "bidirectional"))
      (node (ref "U$46") (pin "MX1") (pinfunction "P0_MX1") (pintype "bidirectional"))
      (node (ref "U$59") (pin "MX1") (pinfunction "P0_MX1") (pintype "bidirectional"))
    )
    (net (code "4") (name "COL2") (class "Default")
      (node (ref "IC1") (pin "39") (pinfunction "(ADC1)PA1_39") (pintype "bidirectional"))
      (node (ref "U$17") (pin "MX1") (pinfunction "P0_MX1") (pintype "bidirectional"))
      (node (ref "U$2") (pin "MX1") (pinfunction "P0_MX1") (pintype "bidirectional"))
      (node (ref "U$32") (pin "MX1") (pinfunction "P0_MX1") (pintype "bidirectional"))
      (node (ref "U$43") (pin "MX1") (pinfunction "P0_MX1") (pintype "bidirectional"))
      (node (ref "U$60") (pin "MX1") (pinfunction "P0_MX1") (pintype "bidirectional"))
    )
    (net (code "5") (name "COL3") (class "Default")
      (node (ref "IC1") (pin "40") (pinfunction "(ADC0)PA0_40") (pintype "bidirectional"))
      (node (ref "U$18") (pin "MX1") (pinfunction "P0_MX1") (pintype "bidirectional"))
      (node (ref "U$3") (pin "MX1") (pinfunction "P0_MX1") (pintype "bidirectional"))
      (node (ref "U$33") (pin "MX1") (pinfunction "P0_MX1") (pintype "bidirectional"))
      (node (ref "U$47") (pin "MX1") (pinfunction "P0_MX1") (pintype "bidirectional"))
      (node (ref "U$61") (pin "MX1") (pinfunction "P0_MX1") (pintype "bidirectional"))
    )
    (net (code "6") (name "COL4") (class "Default")
      (node (ref "IC1") (pin "5") (pinfunction "(SS)PB4_5") (pintype "bidirectional"))
      (node (ref "U$19") (pin "MX1") (pinfunction "P0_MX1") (pintype "bidirectional"))
      (node (ref "U$34") (pin "MX1") (pinfunction "P0_MX1") (pintype "bidirectional"))
      (node (ref "U$4") (pin "MX1") (pinfunction "P0_MX1") (pintype "bidirectional"))
      (node (ref "U$48") (pin "MX1") (pinfunction "P0_MX1") (pintype "bidirectional"))
      (node (ref "U$62") (pin "MX1") (pinfunction "P0_MX1") (pintype "bidirectional"))
    )
    (net (code "7") (name "COL5") (class "Default")
      (node (ref "IC1") (pin "4") (pinfunction "(AIN1/OC0)PB3_4") (pintype "bidirectional"))
      (node (ref "U$20") (pin "MX1") (pinfunction "P0_MX1") (pintype "bidirectional"))
      (node (ref "U$35") (pin "MX1") (pinfunction "P0_MX1") (pintype "bidirectional"))
      (node (ref "U$49") (pin "MX1") (pinfunction "P0_MX1") (pintype "bidirectional"))
      (node (ref "U$5") (pin "MX1") (pinfunction "P0_MX1") (pintype "bidirectional"))
      (node (ref "U$63") (pin "MX1") (pinfunction "P0_MX1") (pintype "bidirectional"))
    )
    (net (code "8") (name "COL6") (class "Default")
      (node (ref "IC1") (pin "3") (pinfunction "(AIN0/INT2)PB2_3") (pintype "bidirectional"))
      (node (ref "U$21") (pin "MX1") (pinfunction "P0_MX1") (pintype "bidirectional"))
      (node (ref "U$36") (pin "MX1") (pinfunction "P0_MX1") (pintype "bidirectional"))
      (node (ref "U$50") (pin "MX1") (pinfunction "P0_MX1") (pintype "bidirectional"))
      (node (ref "U$6") (pin "MX1") (pinfunction "P0_MX1") (pintype "bidirectional"))
      (node (ref "U$64") (pin "MX1") (pinfunction "P0_MX1") (pintype "bidirectional"))
    )
    (net (code "9") (name "COL7") (class "Default")
      (node (ref "IC1") (pin "2") (pinfunction "(T1)PB1_2") (pintype "bidirectional"))
      (node (ref "U$22") (pin "MX1") (pinfunction "P0_MX1") (pintype "bidirectional"))
      (node (ref "U$37") (pin "MX1") (pinfunction "P0_MX1") (pintype "bidirectional"))
      (node (ref "U$51") (pin "MX1") (pinfunction "P0_MX1") (pintype "bidirectional"))
      (node (ref "U$65") (pin "MX1") (pinfunction "P0_MX1") (pintype "bidirectional"))
      (node (ref "U$7") (pin "MX1") (pinfunction "P0_MX1") (pintype "bidirectional"))
    )
    (net (code "10") (name "COL8") (class "Default")
      (node (ref "IC1") (pin "1") (pinfunction "(T0/XCK)PB0_1") (pintype "bidirectional"))
      (node (ref "U$23") (pin "MX1") (pinfunction "P0_MX1") (pintype "bidirectional"))
      (node (ref "U$38") (pin "MX1") (pinfunction "P0_MX1") (pintype "bidirectional"))
      (node (ref "U$52") (pin "MX1") (pinfunction "P0_MX1") (pintype "bidirectional"))
      (node (ref "U$66") (pin "MX1") (pinfunction "P0_MX1") (pintype "bidirectional"))
      (node (ref "U$8") (pin "MX1") (pinfunction "P0_MX1") (pintype "bidirectional"))
    )
    (net (code "11") (name "COL9") (class "Default")
      (node (ref "IC1") (pin "29") (pinfunction "(TOSC2)PC7_29") (pintype "bidirectional"))
      (node (ref "U$24") (pin "MX1") (pinfunction "P0_MX1") (pintype "bidirectional"))
      (node (ref "U$39") (pin "MX1") (pinfunction "P0_MX1") (pintype "bidirectional"))
      (node (ref "U$53") (pin "MX1") (pinfunction "P0_MX1") (pintype "bidirectional"))
      (node (ref "U$67") (pin "MX1") (pinfunction "P0_MX1") (pintype "bidirectional"))
      (node (ref "U$9") (pin "MX1") (pinfunction "P0_MX1") (pintype "bidirectional"))
    )
    (net (code "12") (name "COL10") (class "Default")
      (node (ref "IC1") (pin "28") (pinfunction "(TOSC1)PC6_28") (pintype "bidirectional"))
      (node (ref "U$15") (pin "MX1") (pinfunction "P0_MX1") (pintype "bidirectional"))
      (node (ref "U$25") (pin "MX1") (pinfunction "P0_MX1") (pintype "bidirectional"))
      (node (ref "U$40") (pin "MX1") (pinfunction "P0_MX1") (pintype "bidirectional"))
      (node (ref "U$54") (pin "MX1") (pinfunction "P0_MX1") (pintype "bidirectional"))
      (node (ref "U$75") (pin "MX1") (pinfunction "P0_MX1") (pintype "bidirectional"))
    )
    (net (code "13") (name "COL11") (class "Default")
      (node (ref "IC1") (pin "27") (pinfunction "(TDI)PC5_27") (pintype "bidirectional"))
      (node (ref "U$14") (pin "MX1") (pinfunction "P0_MX1") (pintype "bidirectional"))
      (node (ref "U$26") (pin "MX1") (pinfunction "P0_MX1") (pintype "bidirectional"))
      (node (ref "U$41") (pin "MX1") (pinfunction "P0_MX1") (pintype "bidirectional"))
      (node (ref "U$55") (pin "MX1") (pinfunction "P0_MX1") (pintype "bidirectional"))
    )
    (net (code "14") (name "COL12") (class "Default")
      (node (ref "IC1") (pin "26") (pinfunction "(TDO)PC4_26") (pintype "bidirectional"))
      (node (ref "U$13") (pin "MX1") (pinfunction "P0_MX1") (pintype "bidirectional"))
      (node (ref "U$27") (pin "MX1") (pinfunction "P0_MX1") (pintype "bidirectional"))
      (node (ref "U$42") (pin "MX1") (pinfunction "P0_MX1") (pintype "bidirectional"))
      (node (ref "U$56") (pin "MX1") (pinfunction "P0_MX1") (pintype "bidirectional"))
    )
    (net (code "15") (name "COL13") (class "Default")
      (node (ref "IC1") (pin "25") (pinfunction "(TMS)PC3_25") (pintype "bidirectional"))
      (node (ref "U$12") (pin "MX1") (pinfunction "P0_MX1") (pintype "bidirectional"))
      (node (ref "U$28") (pin "MX1") (pinfunction "P0_MX1") (pintype "bidirectional"))
      (node (ref "U$44") (pin "MX1") (pinfunction "P0_MX1") (pintype "bidirectional"))
      (node (ref "U$57") (pin "MX1") (pinfunction "P0_MX1") (pintype "bidirectional"))
    )
    (net (code "16") (name "COL14") (class "Default")
      (node (ref "IC1") (pin "24") (pinfunction "(TCK)PC2_24") (pintype "bidirectional"))
      (node (ref "U$10") (pin "MX1") (pinfunction "P0_MX1") (pintype "bidirectional"))
      (node (ref "U$29") (pin "MX1") (pinfunction "P0_MX1") (pintype "bidirectional"))
      (node (ref "U$45") (pin "MX1") (pinfunction "P0_MX1") (pintype "bidirectional"))
      (node (ref "U$58") (pin "MX1") (pinfunction "P0_MX1") (pintype "bidirectional"))
    )
    (net (code "17") (name "COL15") (class "Default")
      (node (ref "IC1") (pin "21") (pinfunction "(OC2)PD7_21") (pintype "bidirectional"))
      (node (ref "U$11") (pin "MX1") (pinfunction "P0_MX1") (pintype "bidirectional"))
      (node (ref "U$30") (pin "MX1") (pinfunction "P0_MX1") (pintype "bidirectional"))
    )
    (net (code "18") (name "D+") (class "Default")
      (node (ref "IC1") (pin "16") (pinfunction "(INT0)PD2_16") (pintype "bidirectional"))
      (node (ref "R6") (pin "P$1") (pinfunction "1_P$1") (pintype "passive"))
    )
    (net (code "19") (name "D-") (class "Default")
      (node (ref "IC1") (pin "17") (pinfunction "(INT1)PD3_17") (pintype "bidirectional"))
      (node (ref "R4") (pin "P$1") (pinfunction "1_P$1") (pintype "passive"))
    )
    (net (code "20") (name "DATA") (class "Default")
      (node (ref "D71") (pin "2") (pinfunction "DIN_2") (pintype "input"))
      (node (ref "R8") (pin "P$1") (pinfunction "1_P$1") (pintype "passive"))
    )
    (net (code "21") (name "GND") (class "Default")
      (node (ref "BOOT") (pin "4") (pinfunction "P1_4") (pintype "passive"))
      (node (ref "D69") (pin "A") (pinfunction "A_A") (pintype "passive"))
      (node (ref "D70") (pin "A") (pinfunction "A_A") (pintype "passive"))
      (node (ref "D71") (pin "1") (pinfunction "VSS_1") (pintype "power_in"))
      (node (ref "D72") (pin "1") (pinfunction "VSS_1") (pintype "power_in"))
      (node (ref "D73") (pin "1") (pinfunction "VSS_1") (pintype "power_in"))
      (node (ref "D74") (pin "1") (pinfunction "VSS_1") (pintype "power_in"))
      (node (ref "D75") (pin "1") (pinfunction "VSS_1") (pintype "power_in"))
      (node (ref "D76") (pin "1") (pinfunction "VSS_1") (pintype "power_in"))
      (node (ref "D77") (pin "1") (pinfunction "VSS_1") (pintype "power_in"))
      (node (ref "D78") (pin "1") (pinfunction "VSS_1") (pintype "power_in"))
      (node (ref "IC1") (pin "11") (pinfunction "GND_11") (pintype "power_in"))
      (node (ref "IC1") (pin "31") (pinfunction "GND_31") (pintype "power_in"))
      (node (ref "IC2") (pin "4") (pinfunction "GND_4") (pintype "power_in"))
      (node (ref "ISP1") (pin "6") (pinfunction "GND_6") (pintype "power_in"))
      (node (ref "J2") (pin "A1/B12") (pinfunction "GND_A1/B12") (pintype "power_in"))
      (node (ref "J2") (pin "B1/A12") (pinfunction "GND_B1/A12") (pintype "power_in"))
      (node (ref "J2") (pin "S1") (pinfunction "GND_S1") (pintype "power_in"))
      (node (ref "J2") (pin "S2") (pinfunction "GND_S2") (pintype "power_in"))
      (node (ref "J2") (pin "S3") (pinfunction "GND_S3") (pintype "power_in"))
      (node (ref "J2") (pin "S4") (pinfunction "GND_S4") (pintype "power_in"))
      (node (ref "LED1") (pin "K") (pinfunction "C_K") (pintype "passive"))
      (node (ref "R2") (pin "P$2") (pinfunction "2_P$2") (pintype "passive"))
      (node (ref "R3") (pin "P$1") (pinfunction "1_P$1") (pintype "passive"))
      (node (ref "RESET") (pin "4") (pinfunction "P1_4") (pintype "passive"))
      (node (ref "SW1") (pin "C") (pinfunction "C_C") (pintype "passive"))
      (node (ref "U$68") (pin "2") (pinfunction "2_2") (pintype "passive"))
      (node (ref "U$69") (pin "1") (pinfunction "1_1") (pintype "passive"))
      (node (ref "U$70") (pin "1") (pinfunction "GND_1") (pintype "power_in"))
      (node (ref "U$71") (pin "1") (pinfunction "1_1") (pintype "passive"))
      (node (ref "U$72") (pin "1") (pinfunction "1_1") (pintype "passive"))
      (node (ref "U$73") (pin "1") (pinfunction "1_1") (pintype "passive"))
    )
    (net (code "22") (name "MISO") (class "Default")
      (node (ref "IC1") (pin "7") (pinfunction "(MISO)PB6_7") (pintype "bidirectional"))
      (node (ref "ISP1") (pin "1") (pinfunction "MISO_1") (pintype "input"))
    )
    (net (code "23") (name "MOSI") (class "Default")
      (node (ref "IC1") (pin "6") (pinfunction "(MOSI)PB5_6") (pintype "bidirectional"))
      (node (ref "ISP1") (pin "4") (pinfunction "MOSI_4") (pintype "output"))
    )
    (net (code "24") (name "Net-(D71-DOUT)") (class "Default")
      (node (ref "D71") (pin "4") (pinfunction "DOUT_4") (pintype "output"))
      (node (ref "D72") (pin "2") (pinfunction "DIN_2") (pintype "input"))
    )
    (net (code "25") (name "Net-(D72-DOUT)") (class "Default")
      (node (ref "D72") (pin "4") (pinfunction "DOUT_4") (pintype "output"))
      (node (ref "D75") (pin "2") (pinfunction "DIN_2") (pintype "input"))
    )
    (net (code "26") (name "Net-(D73-DIN)") (class "Default")
      (node (ref "D73") (pin "2") (pinfunction "DIN_2") (pintype "input"))
      (node (ref "D74") (pin "4") (pinfunction "DOUT_4") (pintype "output"))
    )
    (net (code "27") (name "Net-(D73-DOUT)") (class "Default")
      (node (ref "D73") (pin "4") (pinfunction "DOUT_4") (pintype "output"))
      (node (ref "D77") (pin "2") (pinfunction "DIN_2") (pintype "input"))
    )
    (net (code "28") (name "Net-(D74-DIN)") (class "Default")
      (node (ref "D74") (pin "2") (pinfunction "DIN_2") (pintype "input"))
      (node (ref "D75") (pin "4") (pinfunction "DOUT_4") (pintype "output"))
    )
    (net (code "29") (name "Net-(D76-DIN)") (class "Default")
      (node (ref "D76") (pin "2") (pinfunction "DIN_2") (pintype "input"))
      (node (ref "D78") (pin "4") (pinfunction "DOUT_4") (pintype "output"))
    )
    (net (code "30") (name "Net-(D77-DOUT)") (class "Default")
      (node (ref "D77") (pin "4") (pinfunction "DOUT_4") (pintype "output"))
      (node (ref "D78") (pin "2") (pinfunction "DIN_2") (pintype "input"))
    )
    (net (code "31") (name "Net-(F1-2)") (class "Default")
      (node (ref "F1") (pin "P$2") (pinfunction "2_P$2") (pintype "bidirectional"))
      (node (ref "J2") (pin "A4/B9") (pinfunction "VBUS_A4/B9") (pintype "power_in"))
      (node (ref "J2") (pin "B4/A9") (pinfunction "VBUS_B4/A9") (pintype "power_in"))
    )
    (net (code "32") (name "Net-(IC1-XTAL1)") (class "Default")
      (node (ref "CRYSTAL") (pin "2") (pinfunction "2_2") (pintype "passive"))
      (node (ref "IC1") (pin "13") (pinfunction "XTAL1_13") (pintype "bidirectional"))
      (node (ref "U$68") (pin "1") (pinfunction "1_1") (pintype "passive"))
    )
    (net (code "33") (name "Net-(IC1-XTAL2)") (class "Default")
      (node (ref "CRYSTAL") (pin "1") (pinfunction "1_1") (pintype "passive"))
      (node (ref "IC1") (pin "12") (pinfunction "XTAL2_12") (pintype "bidirectional"))
      (node (ref "U$69") (pin "2") (pinfunction "2_2") (pintype "passive"))
    )
    (net (code "34") (name "Net-(IC2A-PB0(MOSI{slash}DI{slash}SDA{slash}AIN0{slash}OC0A{slash}~{OC1A}{slash}AREF{slash}PCINT0))") (class "Default")
      (node (ref "IC2") (pin "5") (pinfunction "PB0(MOSI/DI/SDA/AIN0/OC0A/~{OC1A}/AREF/PCINT0)_5") (pintype "bidirectional"))
      (node (ref "R8") (pin "P$2") (pinfunction "2_P$2") (pintype "passive"))
    )
    (net (code "35") (name "Net-(J2-CC1)") (class "Default")
      (node (ref "J2") (pin "A5") (pinfunction "CC1_A5") (pintype "bidirectional"))
      (node (ref "R3") (pin "P$2") (pinfunction "2_P$2") (pintype "passive"))
    )
    (net (code "36") (name "Net-(J2-CC2)") (class "Default")
      (node (ref "J2") (pin "B5") (pinfunction "CC2_B5") (pintype "bidirectional"))
      (node (ref "R2") (pin "P$1") (pinfunction "1_P$1") (pintype "passive"))
    )
    (net (code "37") (name "Net-(J2-DN1)") (class "Default")
      (node (ref "D69") (pin "C") (pinfunction "C_C") (pintype "passive"))
      (node (ref "J2") (pin "A7") (pinfunction "DN1_A7") (pintype "bidirectional"))
      (node (ref "J2") (pin "B7") (pinfunction "DN2_B7") (pintype "bidirectional"))
      (node (ref "R4") (pin "P$2") (pinfunction "2_P$2") (pintype "passive"))
      (node (ref "R7") (pin "P$1") (pinfunction "1_P$1") (pintype "passive"))
    )
    (net (code "38") (name "Net-(J2-DP1)") (class "Default")
      (node (ref "D70") (pin "C") (pinfunction "C_C") (pintype "passive"))
      (node (ref "J2") (pin "A6") (pinfunction "DP1_A6") (pintype "bidirectional"))
      (node (ref "J2") (pin "B6") (pinfunction "DP2_B6") (pintype "bidirectional"))
      (node (ref "R6") (pin "P$2") (pinfunction "2_P$2") (pintype "passive"))
    )
    (net (code "39") (name "Net-(R1-1)") (class "Default")
      (node (ref "R1") (pin "P$1") (pinfunction "1_P$1") (pintype "passive"))
      (node (ref "RESET") (pin "2") (pinfunction "S1_2") (pintype "passive"))
    )
    (net (code "40") (name "Net-(R5-2)") (class "Default")
      (node (ref "LED1") (pin "A") (pinfunction "A_A") (pintype "passive"))
      (node (ref "R5") (pin "P$2") (pinfunction "2_P$2") (pintype "passive"))
    )
    (net (code "41") (name "Net-(U$1-P1)") (class "Default")
      (node (ref "D1") (pin "A") (pinfunction "A_A") (pintype "passive"))
      (node (ref "U$1") (pin "MX2") (pinfunction "P1_MX2") (pintype "bidirectional"))
    )
    (net (code "42") (name "Net-(U$2-P1)") (class "Default")
      (node (ref "D2") (pin "A") (pinfunction "A_A") (pintype "passive"))
      (node (ref "U$2") (pin "MX2") (pinfunction "P1_MX2") (pintype "bidirectional"))
    )
    (net (code "43") (name "Net-(U$3-P1)") (class "Default")
      (node (ref "D3") (pin "A") (pinfunction "A_A") (pintype "passive"))
      (node (ref "U$3") (pin "MX2") (pinfunction "P1_MX2") (pintype "bidirectional"))
    )
    (net (code "44") (name "Net-(U$4-P1)") (class "Default")
      (node (ref "D4") (pin "A") (pinfunction "A_A") (pintype "passive"))
      (node (ref "U$4") (pin "MX2") (pinfunction "P1_MX2") (pintype "bidirectional"))
    )
    (net (code "45") (name "Net-(U$5-P1)") (class "Default")
      (node (ref "D5") (pin "A") (pinfunction "A_A") (pintype "passive"))
      (node (ref "U$5") (pin "MX2") (pinfunction "P1_MX2") (pintype "bidirectional"))
    )
    (net (code "46") (name "Net-(U$6-P1)") (class "Default")
      (node (ref "D6") (pin "A") (pinfunction "A_A") (pintype "passive"))
      (node (ref "U$6") (pin "MX2") (pinfunction "P1_MX2") (pintype "bidirectional"))
    )
    (net (code "47") (name "Net-(U$7-P1)") (class "Default")
      (node (ref "D7") (pin "A") (pinfunction "A_A") (pintype "passive"))
      (node (ref "U$7") (pin "MX2") (pinfunction "P1_MX2") (pintype "bidirectional"))
    )
    (net (code "48") (name "Net-(U$8-P1)") (class "Default")
      (node (ref "D8") (pin "A") (pinfunction "A_A") (pintype "passive"))
      (node (ref "U$8") (pin "MX2") (pinfunction "P1_MX2") (pintype "bidirectional"))
    )
    (net (code "49") (name "Net-(U$9-P1)") (class "Default")
      (node (ref "D9") (pin "A") (pinfunction "A_A") (pintype "passive"))
      (node (ref "U$9") (pin "MX2") (pinfunction "P1_MX2") (pintype "bidirectional"))
    )
    (net (code "50") (name "Net-(U$10-P1)") (class "Default")
      (node (ref "D14") (pin "A") (pinfunction "A_A") (pintype "passive"))
      (node (ref "U$10") (pin "MX2") (pinfunction "P1_MX2") (pintype "bidirectional"))
    )
    (net (code "51") (name "Net-(U$11-P1)") (class "Default")
      (node (ref "D15") (pin "A") (pinfunction "A_A") (pintype "passive"))
      (node (ref "U$11") (pin "MX2") (pinfunction "P1_MX2") (pintype "bidirectional"))
    )
    (net (code "52") (name "Net-(U$12-P1)") (class "Default")
      (node (ref "D13") (pin "A") (pinfunction "A_A") (pintype "passive"))
      (node (ref "U$12") (pin "MX2") (pinfunction "P1_MX2") (pintype "bidirectional"))
    )
    (net (code "53") (name "Net-(U$13-P1)") (class "Default")
      (node (ref "D12") (pin "A") (pinfunction "A_A") (pintype "passive"))
      (node (ref "U$13") (pin "MX2") (pinfunction "P1_MX2") (pintype "bidirectional"))
    )
    (net (code "54") (name "Net-(U$14-P1)") (class "Default")
      (node (ref "D11") (pin "A") (pinfunction "A_A") (pintype "passive"))
      (node (ref "U$14") (pin "MX2") (pinfunction "P1_MX2") (pintype "bidirectional"))
    )
    (net (code "55") (name "Net-(U$15-P1)") (class "Default")
      (node (ref "D10") (pin "A") (pinfunction "A_A") (pintype "passive"))
      (node (ref "U$15") (pin "MX2") (pinfunction "P1_MX2") (pintype "bidirectional"))
    )
    (net (code "56") (name "Net-(U$16-P1)") (class "Default")
      (node (ref "D30") (pin "A") (pinfunction "A_A") (pintype "passive"))
      (node (ref "U$16") (pin "MX2") (pinfunction "P1_MX2") (pintype "bidirectional"))
    )
    (net (code "57") (name "Net-(U$17-P1)") (class "Default")
      (node (ref "D29") (pin "A") (pinfunction "A_A") (pintype "passive"))
      (node (ref "U$17") (pin "MX2") (pinfunction "P1_MX2") (pintype "bidirectional"))
    )
    (net (code "58") (name "Net-(U$18-P1)") (class "Default")
      (node (ref "D28") (pin "A") (pinfunction "A_A") (pintype "passive"))
      (node (ref "U$18") (pin "MX2") (pinfunction "P1_MX2") (pintype "bidirectional"))
    )
    (net (code "59") (name "Net-(U$19-P1)") (class "Default")
      (node (ref "D27") (pin "A") (pinfunction "A_A") (pintype "passive"))
      (node (ref "U$19") (pin "MX2") (pinfunction "P1_MX2") (pintype "bidirectional"))
    )
    (net (code "60") (name "Net-(U$20-P1)") (class "Default")
      (node (ref "D26") (pin "A") (pinfunction "A_A") (pintype "passive"))
      (node (ref "U$20") (pin "MX2") (pinfunction "P1_MX2") (pintype "bidirectional"))
    )
    (net (code "61") (name "Net-(U$21-P1)") (class "Default")
      (node (ref "D25") (pin "A") (pinfunction "A_A") (pintype "passive"))
      (node (ref "U$21") (pin "MX2") (pinfunction "P1_MX2") (pintype "bidirectional"))
    )
    (net (code "62") (name "Net-(U$22-P1)") (class "Default")
      (node (ref "D24") (pin "A") (pinfunction "A_A") (pintype "passive"))
      (node (ref "U$22") (pin "MX2") (pinfunction "P1_MX2") (pintype "bidirectional"))
    )
    (net (code "63") (name "Net-(U$23-P1)") (class "Default")
      (node (ref "D23") (pin "A") (pinfunction "A_A") (pintype "passive"))
      (node (ref "U$23") (pin "MX2") (pinfunction "P1_MX2") (pintype "bidirectional"))
    )
    (net (code "64") (name "Net-(U$24-P1)") (class "Default")
      (node (ref "D22") (pin "A") (pinfunction "A_A") (pintype "passive"))
      (node (ref "U$24") (pin "MX2") (pinfunction "P1_MX2") (pintype "bidirectional"))
    )
    (net (code "65") (name "Net-(U$25-P1)") (class "Default")
      (node (ref "D21") (pin "A") (pinfunction "A_A") (pintype "passive"))
      (node (ref "U$25") (pin "MX2") (pinfunction "P1_MX2") (pintype "bidirectional"))
    )
    (net (code "66") (name "Net-(U$26-P1)") (class "Default")
      (node (ref "D20") (pin "A") (pinfunction "A_A") (pintype "passive"))
      (node (ref "U$26") (pin "MX2") (pinfunction "P1_MX2") (pintype "bidirectional"))
    )
    (net (code "67") (name "Net-(U$27-P1)") (class "Default")
      (node (ref "D19") (pin "A") (pinfunction "A_A") (pintype "passive"))
      (node (ref "U$27") (pin "MX2") (pinfunction "P1_MX2") (pintype "bidirectional"))
    )
    (net (code "68") (name "Net-(U$28-P1)") (class "Default")
      (node (ref "D18") (pin "A") (pinfunction "A_A") (pintype "passive"))
      (node (ref "U$28") (pin "MX2") (pinfunction "P1_MX2") (pintype "bidirectional"))
    )
    (net (code "69") (name "Net-(U$29-P1)") (class "Default")
      (node (ref "D17") (pin "A") (pinfunction "A_A") (pintype "passive"))
      (node (ref "U$29") (pin "MX2") (pinfunction "P1_MX2") (pintype "bidirectional"))
    )
    (net (code "70") (name "Net-(U$30-P1)") (class "Default")
      (node (ref "D16") (pin "A") (pinfunction "A_A") (pintype "passive"))
      (node (ref "U$30") (pin "MX2") (pinfunction "P1_MX2") (pintype "bidirectional"))
    )
    (net (code "71") (name "Net-(U$31-P1)") (class "Default")
      (node (ref "D44") (pin "A") (pinfunction "A_A") (pintype "passive"))
      (node (ref "U$31") (pin "MX2") (pinfunction "P1_MX2") (pintype "bidirectional"))
    )
    (net (code "72") (name "Net-(U$32-P1)") (class "Default")
      (node (ref "D43") (pin "A") (pinfunction "A_A") (pintype "passive"))
      (node (ref "U$32") (pin "MX2") (pinfunction "P1_MX2") (pintype "bidirectional"))
    )
    (net (code "73") (name "Net-(U$33-P1)") (class "Default")
      (node (ref "D42") (pin "A") (pinfunction "A_A") (pintype "passive"))
      (node (ref "U$33") (pin "MX2") (pinfunction "P1_MX2") (pintype "bidirectional"))
    )
    (net (code "74") (name "Net-(U$34-P1)") (class "Default")
      (node (ref "D41") (pin "A") (pinfunction "A_A") (pintype "passive"))
      (node (ref "U$34") (pin "MX2") (pinfunction "P1_MX2") (pintype "bidirectional"))
    )
    (net (code "75") (name "Net-(U$35-P1)") (class "Default")
      (node (ref "D40") (pin "A") (pinfunction "A_A") (pintype "passive"))
      (node (ref "U$35") (pin "MX2") (pinfunction "P1_MX2") (pintype "bidirectional"))
    )
    (net (code "76") (name "Net-(U$36-P1)") (class "Default")
      (node (ref "D39") (pin "A") (pinfunction "A_A") (pintype "passive"))
      (node (ref "U$36") (pin "MX2") (pinfunction "P1_MX2") (pintype "bidirectional"))
    )
    (net (code "77") (name "Net-(U$37-P1)") (class "Default")
      (node (ref "D38") (pin "A") (pinfunction "A_A") (pintype "passive"))
      (node (ref "U$37") (pin "MX2") (pinfunction "P1_MX2") (pintype "bidirectional"))
    )
    (net (code "78") (name "Net-(U$38-P1)") (class "Default")
      (node (ref "D37") (pin "A") (pinfunction "A_A") (pintype "passive"))
      (node (ref "U$38") (pin "MX2") (pinfunction "P1_MX2") (pintype "bidirectional"))
    )
    (net (code "79") (name "Net-(U$39-P1)") (class "Default")
      (node (ref "D36") (pin "A") (pinfunction "A_A") (pintype "passive"))
      (node (ref "U$39") (pin "MX2") (pinfunction "P1_MX2") (pintype "bidirectional"))
    )
    (net (code "80") (name "Net-(U$40-P1)") (class "Default")
      (node (ref "D35") (pin "A") (pinfunction "A_A") (pintype "passive"))
      (node (ref "U$40") (pin "MX2") (pinfunction "P1_MX2") (pintype "bidirectional"))
    )
    (net (code "81") (name "Net-(U$41-P1)") (class "Default")
      (node (ref "D34") (pin "A") (pinfunction "A_A") (pintype "passive"))
      (node (ref "U$41") (pin "MX2") (pinfunction "P1_MX2") (pintype "bidirectional"))
    )
    (net (code "82") (name "Net-(U$42-P1)") (class "Default")
      (node (ref "D33") (pin "A") (pinfunction "A_A") (pintype "passive"))
      (node (ref "U$42") (pin "MX2") (pinfunction "P1_MX2") (pintype "bidirectional"))
    )
    (net (code "83") (name "Net-(U$43-P1)") (class "Default")
      (node (ref "D46") (pin "A") (pinfunction "A_A") (pintype "passive"))
      (node (ref "U$43") (pin "MX2") (pinfunction "P1_MX2") (pintype "bidirectional"))
    )
    (net (code "84") (name "Net-(U$44-P1)") (class "Default")
      (node (ref "D32") (pin "A") (pinfunction "A_A") (pintype "passive"))
      (node (ref "U$44") (pin "MX2") (pinfunction "P1_MX2") (pintype "bidirectional"))
    )
    (net (code "85") (name "Net-(U$45-P1)") (class "Default")
      (node (ref "D31") (pin "A") (pinfunction "A_A") (pintype "passive"))
      (node (ref "U$45") (pin "MX2") (pinfunction "P1_MX2") (pintype "bidirectional"))
    )
    (net (code "86") (name "Net-(U$46-P1)") (class "Default")
      (node (ref "D45") (pin "A") (pinfunction "A_A") (pintype "passive"))
      (node (ref "U$46") (pin "MX2") (pinfunction "P1_MX2") (pintype "bidirectional"))
    )
    (net (code "87") (name "Net-(U$47-P1)") (class "Default")
      (node (ref "D47") (pin "A") (pinfunction "A_A") (pintype "passive"))
      (node (ref "U$47") (pin "MX2") (pinfunction "P1_MX2") (pintype "bidirectional"))
    )
    (net (code "88") (name "Net-(U$48-P1)") (class "Default")
      (node (ref "D48") (pin "A") (pinfunction "A_A") (pintype "passive"))
      (node (ref "U$48") (pin "MX2") (pinfunction "P1_MX2") (pintype "bidirectional"))
    )
    (net (code "89") (name "Net-(U$49-P1)") (class "Default")
      (node (ref "D49") (pin "A") (pinfunction "A_A") (pintype "passive"))
      (node (ref "U$49") (pin "MX2") (pinfunction "P1_MX2") (pintype "bidirectional"))
    )
    (net (code "90") (name "Net-(U$50-P1)") (class "Default")
      (node (ref "D50") (pin "A") (pinfunction "A_A") (pintype "passive"))
      (node (ref "U$50") (pin "MX2") (pinfunction "P1_MX2") (pintype "bidirectional"))
    )
    (net (code "91") (name "Net-(U$51-P1)") (class "Default")
      (node (ref "D51") (pin "A") (pinfunction "A_A") (pintype "passive"))
      (node (ref "U$51") (pin "MX2") (pinfunction "P1_MX2") (pintype "bidirectional"))
    )
    (net (code "92") (name "Net-(U$52-P1)") (class "Default")
      (node (ref "D52") (pin "A") (pinfunction "A_A") (pintype "passive"))
      (node (ref "U$52") (pin "MX2") (pinfunction "P1_MX2") (pintype "bidirectional"))
    )
    (net (code "93") (name "Net-(U$53-P1)") (class "Default")
      (node (ref "D53") (pin "A") (pinfunction "A_A") (pintype "passive"))
      (node (ref "U$53") (pin "MX2") (pinfunction "P1_MX2") (pintype "bidirectional"))
    )
    (net (code "94") (name "Net-(U$54-P1)") (class "Default")
      (node (ref "D54") (pin "A") (pinfunction "A_A") (pintype "passive"))
      (node (ref "U$54") (pin "MX2") (pinfunction "P1_MX2") (pintype "bidirectional"))
    )
    (net (code "95") (name "Net-(U$55-P1)") (class "Default")
      (node (ref "D55") (pin "A") (pinfunction "A_A") (pintype "passive"))
      (node (ref "U$55") (pin "MX2") (pinfunction "P1_MX2") (pintype "bidirectional"))
    )
    (net (code "96") (name "Net-(U$56-P1)") (class "Default")
      (node (ref "D56") (pin "A") (pinfunction "A_A") (pintype "passive"))
      (node (ref "U$56") (pin "MX2") (pinfunction "P1_MX2") (pintype "bidirectional"))
    )
    (net (code "97") (name "Net-(U$57-P1)") (class "Default")
      (node (ref "D57") (pin "A") (pinfunction "A_A") (pintype "passive"))
      (node (ref "U$57") (pin "MX2") (pinfunction "P1_MX2") (pintype "bidirectional"))
    )
    (net (code "98") (name "Net-(U$58-P1)") (class "Default")
      (node (ref "D58") (pin "A") (pinfunction "A_A") (pintype "passive"))
      (node (ref "U$58") (pin "MX2") (pinfunction "P1_MX2") (pintype "bidirectional"))
    )
    (net (code "99") (name "Net-(U$59-P1)") (class "Default")
      (node (ref "D59") (pin "A") (pinfunction "A_A") (pintype "passive"))
      (node (ref "U$59") (pin "MX2") (pinfunction "P1_MX2") (pintype "bidirectional"))
    )
    (net (code "100") (name "Net-(U$60-P1)") (class "Default")
      (node (ref "D60") (pin "A") (pinfunction "A_A") (pintype "passive"))
      (node (ref "U$60") (pin "MX2") (pinfunction "P1_MX2") (pintype "bidirectional"))
    )
    (net (code "101") (name "Net-(U$61-P1)") (class "Default")
      (node (ref "D61") (pin "A") (pinfunction "A_A") (pintype "passive"))
      (node (ref "U$61") (pin "MX2") (pinfunction "P1_MX2") (pintype "bidirectional"))
    )
    (net (code "102") (name "Net-(U$62-P1)") (class "Default")
      (node (ref "D62") (pin "A") (pinfunction "A_A") (pintype "passive"))
      (node (ref "U$62") (pin "MX2") (pinfunction "P1_MX2") (pintype "bidirectional"))
    )
    (net (code "103") (name "Net-(U$63-P1)") (class "Default")
      (node (ref "D63") (pin "A") (pinfunction "A_A") (pintype "passive"))
      (node (ref "U$63") (pin "MX2") (pinfunction "P1_MX2") (pintype "bidirectional"))
    )
    (net (code "104") (name "Net-(U$64-P1)") (class "Default")
      (node (ref "D64") (pin "A") (pinfunction "A_A") (pintype "passive"))
      (node (ref "U$64") (pin "MX2") (pinfunction "P1_MX2") (pintype "bidirectional"))
    )
    (net (code "105") (name "Net-(U$65-P1)") (class "Default")
      (node (ref "D65") (pin "A") (pinfunction "A_A") (pintype "passive"))
      (node (ref "U$65") (pin "MX2") (pinfunction "P1_MX2") (pintype "bidirectional"))
    )
    (net (code "106") (name "Net-(U$66-P1)") (class "Default")
      (node (ref "D66") (pin "A") (pinfunction "A_A") (pintype "passive"))
      (node (ref "U$66") (pin "MX2") (pinfunction "P1_MX2") (pintype "bidirectional"))
    )
    (net (code "107") (name "Net-(U$67-P1)") (class "Default")
      (node (ref "D67") (pin "A") (pinfunction "A_A") (pintype "passive"))
      (node (ref "U$67") (pin "MX2") (pinfunction "P1_MX2") (pintype "bidirectional"))
    )
    (net (code "108") (name "Net-(U$75-P1)") (class "Default")
      (node (ref "D68") (pin "A") (pinfunction "A_A") (pintype "passive"))
      (node (ref "U$75") (pin "MX2") (pinfunction "P1_MX2") (pintype "bidirectional"))
    )
    (net (code "109") (name "OUTA") (class "Default")
      (node (ref "IC1") (pin "19") (pinfunction "(OC1A)PD5_19") (pintype "bidirectional"))
      (node (ref "SW1") (pin "A") (pinfunction "A_A") (pintype "passive"))
    )
    (net (code "110") (name "OUTB") (class "Default")
      (node (ref "IC1") (pin "20") (pinfunction "(ICP)PD6_20") (pintype "bidirectional"))
      (node (ref "SW1") (pin "B") (pinfunction "B_B") (pintype "passive"))
    )
    (net (code "111") (name "ROW1") (class "Default")
      (node (ref "D1") (pin "C") (pinfunction "C_C") (pintype "passive"))
      (node (ref "D10") (pin "C") (pinfunction "C_C") (pintype "passive"))
      (node (ref "D11") (pin "C") (pinfunction "C_C") (pintype "passive"))
      (node (ref "D12") (pin "C") (pinfunction "C_C") (pintype "passive"))
      (node (ref "D13") (pin "C") (pinfunction "C_C") (pintype "passive"))
      (node (ref "D14") (pin "C") (pinfunction "C_C") (pintype "passive"))
      (node (ref "D15") (pin "C") (pinfunction "C_C") (pintype "passive"))
      (node (ref "D2") (pin "C") (pinfunction "C_C") (pintype "passive"))
      (node (ref "D3") (pin "C") (pinfunction "C_C") (pintype "passive"))
      (node (ref "D4") (pin "C") (pinfunction "C_C") (pintype "passive"))
      (node (ref "D5") (pin "C") (pinfunction "C_C") (pintype "passive"))
      (node (ref "D6") (pin "C") (pinfunction "C_C") (pintype "passive"))
      (node (ref "D7") (pin "C") (pinfunction "C_C") (pintype "passive"))
      (node (ref "D8") (pin "C") (pinfunction "C_C") (pintype "passive"))
      (node (ref "D9") (pin "C") (pinfunction "C_C") (pintype "passive"))
      (node (ref "IC1") (pin "33") (pinfunction "(ADC7)PA7_33") (pintype "bidirectional"))
    )
    (net (code "112") (name "ROW2") (class "Default")
      (node (ref "D16") (pin "C") (pinfunction "C_C") (pintype "passive"))
      (node (ref "D17") (pin "C") (pinfunction "C_C") (pintype "passive"))
      (node (ref "D18") (pin "C") (pinfunction "C_C") (pintype "passive"))
      (node (ref "D19") (pin "C") (pinfunction "C_C") (pintype "passive"))
      (node (ref "D20") (pin "C") (pinfunction "C_C") (pintype "passive"))
      (node (ref "D21") (pin "C") (pinfunction "C_C") (pintype "passive"))
      (node (ref "D22") (pin "C") (pinfunction "C_C") (pintype "passive"))
      (node (ref "D23") (pin "C") (pinfunction "C_C") (pintype "passive"))
      (node (ref "D24") (pin "C") (pinfunction "C_C") (pintype "passive"))
      (node (ref "D25") (pin "C") (pinfunction "C_C") (pintype "passive"))
      (node (ref "D26") (pin "C") (pinfunction "C_C") (pintype "passive"))
      (node (ref "D27") (pin "C") (pinfunction "C_C") (pintype "passive"))
      (node (ref "D28") (pin "C") (pinfunction "C_C") (pintype "passive"))
      (node (ref "D29") (pin "C") (pinfunction "C_C") (pintype "passive"))
      (node (ref "D30") (pin "C") (pinfunction "C_C") (pintype "passive"))
      (node (ref "IC1") (pin "34") (pinfunction "(ADC6)PA6_34") (pintype "bidirectional"))
    )
    (net (code "113") (name "ROW3") (class "Default")
      (node (ref "D31") (pin "C") (pinfunction "C_C") (pintype "passive"))
      (node (ref "D32") (pin "C") (pinfunction "C_C") (pintype "passive"))
      (node (ref "D33") (pin "C") (pinfunction "C_C") (pintype "passive"))
      (node (ref "D34") (pin "C") (pinfunction "C_C") (pintype "passive"))
      (node (ref "D35") (pin "C") (pinfunction "C_C") (pintype "passive"))
      (node (ref "D36") (pin "C") (pinfunction "C_C") (pintype "passive"))
      (node (ref "D37") (pin "C") (pinfunction "C_C") (pintype "passive"))
      (node (ref "D38") (pin "C") (pinfunction "C_C") (pintype "passive"))
      (node (ref "D39") (pin "C") (pinfunction "C_C") (pintype "passive"))
      (node (ref "D40") (pin "C") (pinfunction "C_C") (pintype "passive"))
      (node (ref "D41") (pin "C") (pinfunction "C_C") (pintype "passive"))
      (node (ref "D42") (pin "C") (pinfunction "C_C") (pintype "passive"))
      (node (ref "D43") (pin "C") (pinfunction "C_C") (pintype "passive"))
      (node (ref "D44") (pin "C") (pinfunction "C_C") (pintype "passive"))
      (node (ref "IC1") (pin "35") (pinfunction "(ADC5)PA5_35") (pintype "bidirectional"))
    )
    (net (code "114") (name "ROW4") (class "Default")
      (node (ref "D45") (pin "C") (pinfunction "C_C") (pintype "passive"))
      (node (ref "D46") (pin "C") (pinfunction "C_C") (pintype "passive"))
      (node (ref "D47") (pin "C") (pinfunction "C_C") (pintype "passive"))
      (node (ref "D48") (pin "C") (pinfunction "C_C") (pintype "passive"))
      (node (ref "D49") (pin "C") (pinfunction "C_C") (pintype "passive"))
      (node (ref "D50") (pin "C") (pinfunction "C_C") (pintype "passive"))
      (node (ref "D51") (pin "C") (pinfunction "C_C") (pintype "passive"))
      (node (ref "D52") (pin "C") (pinfunction "C_C") (pintype "passive"))
      (node (ref "D53") (pin "C") (pinfunction "C_C") (pintype "passive"))
      (node (ref "D54") (pin "C") (pinfunction "C_C") (pintype "passive"))
      (node (ref "D55") (pin "C") (pinfunction "C_C") (pintype "passive"))
      (node (ref "D56") (pin "C") (pinfunction "C_C") (pintype "passive"))
      (node (ref "D57") (pin "C") (pinfunction "C_C") (pintype "passive"))
      (node (ref "D58") (pin "C") (pinfunction "C_C") (pintype "passive"))
      (node (ref "IC1") (pin "36") (pinfunction "(ADC4)PA4_36") (pintype "bidirectional"))
    )
    (net (code "115") (name "ROW5") (class "Default")
      (node (ref "D59") (pin "C") (pinfunction "C_C") (pintype "passive"))
      (node (ref "D60") (pin "C") (pinfunction "C_C") (pintype "passive"))
      (node (ref "D61") (pin "C") (pinfunction "C_C") (pintype "passive"))
      (node (ref "D62") (pin "C") (pinfunction "C_C") (pintype "passive"))
      (node (ref "D63") (pin "C") (pinfunction "C_C") (pintype "passive"))
      (node (ref "D64") (pin "C") (pinfunction "C_C") (pintype "passive"))
      (node (ref "D65") (pin "C") (pinfunction "C_C") (pintype "passive"))
      (node (ref "D66") (pin "C") (pinfunction "C_C") (pintype "passive"))
      (node (ref "D67") (pin "C") (pinfunction "C_C") (pintype "passive"))
      (node (ref "D68") (pin "C") (pinfunction "C_C") (pintype "passive"))
      (node (ref "IC1") (pin "37") (pinfunction "(ADC3)PA3_37") (pintype "bidirectional"))
    )
    (net (code "116") (name "RST") (class "Default")
      (node (ref "IC1") (pin "9") (pinfunction "RESET_9") (pintype "input"))
      (node (ref "ISP1") (pin "5") (pinfunction "RST_5") (pintype "output"))
      (node (ref "RESET") (pin "1") (pinfunction "S_1") (pintype "passive"))
    )
    (net (code "117") (name "SCK") (class "Default")
      (node (ref "IC1") (pin "8") (pinfunction "(SCK)PB7_8") (pintype "bidirectional"))
      (node (ref "ISP1") (pin "3") (pinfunction "SCK_3") (pintype "output"))
    )
    (net (code "118") (name "SCL") (class "Default")
      (node (ref "IC1") (pin "22") (pinfunction "(SCL)PC0_22") (pintype "bidirectional"))
      (node (ref "U$70") (pin "3") (pinfunction "SCL_3") (pintype "bidirectional"))
    )
    (net (code "119") (name "SDA") (class "Default")
      (node (ref "IC1") (pin "23") (pinfunction "(SDA)PC1_23") (pintype "bidirectional"))
      (node (ref "U$70") (pin "4") (pinfunction "SDA_4") (pintype "bidirectional"))
    )
    (net (code "120") (name "unconnected-(BOOT-P-Pad3)") (class "Default")
      (node (ref "BOOT") (pin "3") (pinfunction "P_3") (pintype "passive"))
    )
    (net (code "121") (name "unconnected-(BOOT-S1-Pad2)") (class "Default")
      (node (ref "BOOT") (pin "2") (pinfunction "S1_2") (pintype "passive"))
    )
    (net (code "122") (name "unconnected-(D76-DOUT-Pad4)") (class "Default")
      (node (ref "D76") (pin "4") (pinfunction "DOUT_4") (pintype "output"))
    )
    (net (code "123") (name "unconnected-(IC1-(RXD)PD0-Pad14)") (class "Default")
      (node (ref "IC1") (pin "14") (pinfunction "(RXD)PD0_14") (pintype "bidirectional"))
    )
    (net (code "124") (name "unconnected-(IC1-(TXD)PD1-Pad15)") (class "Default")
      (node (ref "IC1") (pin "15") (pinfunction "(TXD)PD1_15") (pintype "bidirectional"))
    )
    (net (code "125") (name "unconnected-(IC1-AREF-Pad32)") (class "Default")
      (node (ref "IC1") (pin "32") (pinfunction "AREF_32") (pintype "passive"))
    )
    (net (code "126") (name "unconnected-(IC2A-PB1(MISO{slash}DO{slash}AIN1{slash}OC0B{slash}OC1A{slash}PCINT1)-Pad6)") (class "Default")
      (node (ref "IC2") (pin "6") (pinfunction "PB1(MISO/DO/AIN1/OC0B/OC1A/PCINT1)_6") (pintype "bidirectional"))
    )
    (net (code "127") (name "unconnected-(IC2A-PB2(SCK{slash}USCK{slash}SCL{slash}ADC1{slash}T0{slash}INT0{slash}PCINT2)-Pad7)") (class "Default")
      (node (ref "IC2") (pin "7") (pinfunction "PB2(SCK/USCK/SCL/ADC1/T0/INT0/PCINT2)_7") (pintype "bidirectional"))
    )
    (net (code "128") (name "unconnected-(IC2A-PB3(ADC3{slash}~{OC1B}{slash}CLKI{slash}XTAL1{slash}PCINT3)-Pad2)") (class "Default")
      (node (ref "IC2") (pin "2") (pinfunction "PB3(ADC3/~{OC1B}/CLKI/XTAL1/PCINT3)_2") (pintype "bidirectional"))
    )
    (net (code "129") (name "unconnected-(IC2A-PB4(ADC2{slash}OC1B{slash}CLKO{slash}XTAL2{slash}PCINT4)-Pad3)") (class "Default")
      (node (ref "IC2") (pin "3") (pinfunction "PB4(ADC2/OC1B/CLKO/XTAL2/PCINT4)_3") (pintype "bidirectional"))
    )
    (net (code "130") (name "unconnected-(IC2A-PB5(DW{slash}ADC0{slash}~{RESET}{slash}PCINT5)-Pad1)") (class "Default")
      (node (ref "IC2") (pin "1") (pinfunction "PB5(DW/ADC0/~{RESET}/PCINT5)_1") (pintype "bidirectional"))
    )
    (net (code "131") (name "unconnected-(J2-SBU1-PadA8)") (class "Default")
      (node (ref "J2") (pin "A8") (pinfunction "SBU1_A8") (pintype "bidirectional"))
    )
    (net (code "132") (name "unconnected-(J2-SBU2-PadB8)") (class "Default")
      (node (ref "J2") (pin "B8") (pinfunction "SBU2_B8") (pintype "bidirectional"))
    )
    (net (code "133") (name "unconnected-(RESET-P-Pad3)") (class "Default")
      (node (ref "RESET") (pin "3") (pinfunction "P_3") (pintype "passive"))
    )
  )
)
